# omni-usb_1_00a.net
KiCad netlist of a schematic drawn in EAGLE
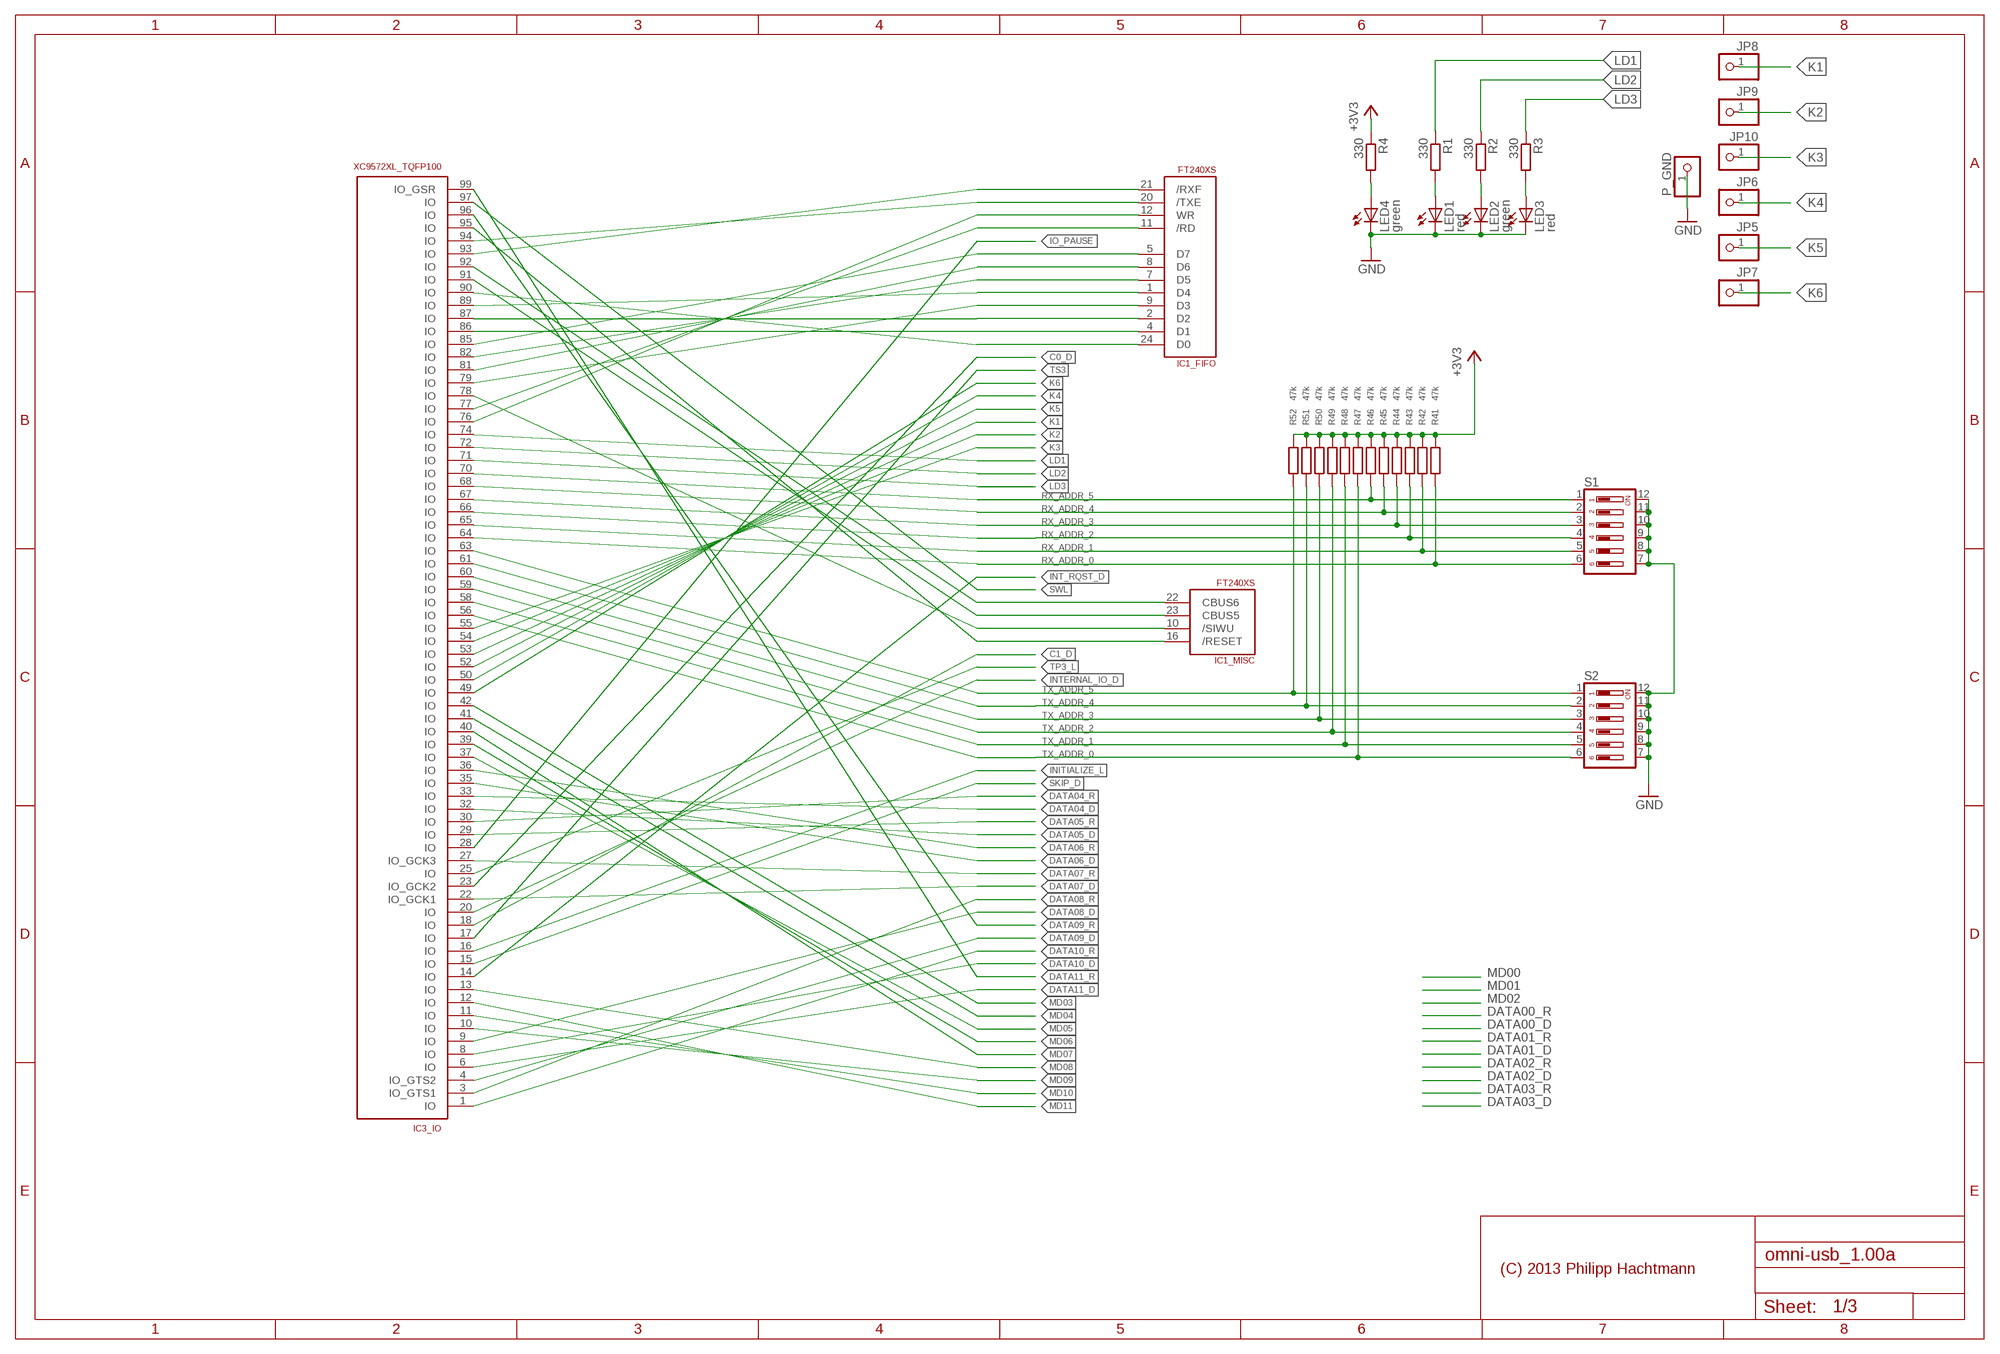
[diagram p0: schematic, sheet 1]
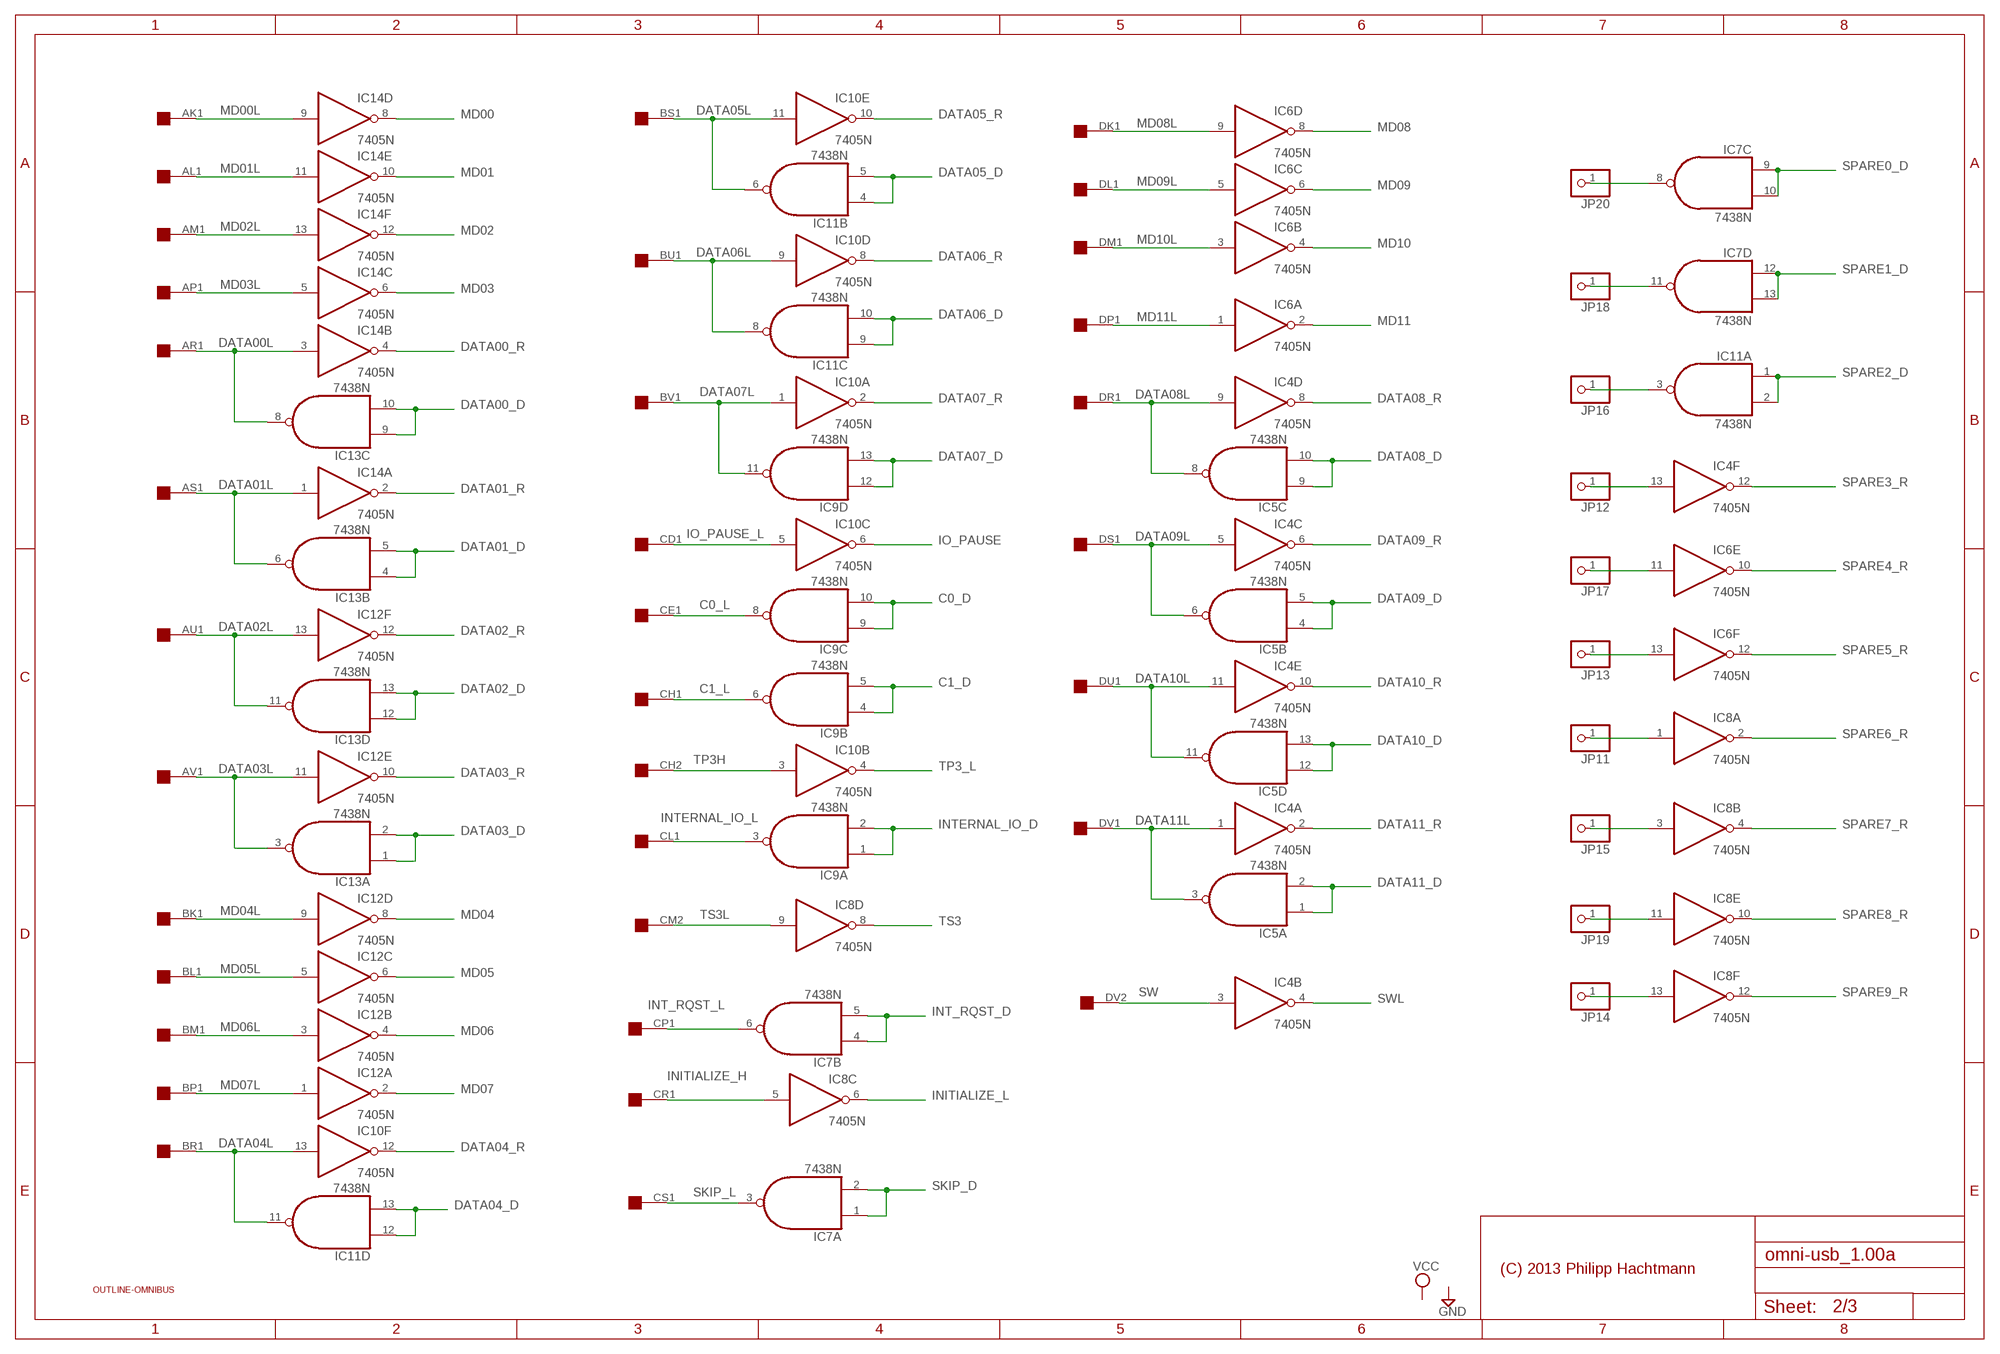
[diagram p1: schematic, sheet 2]
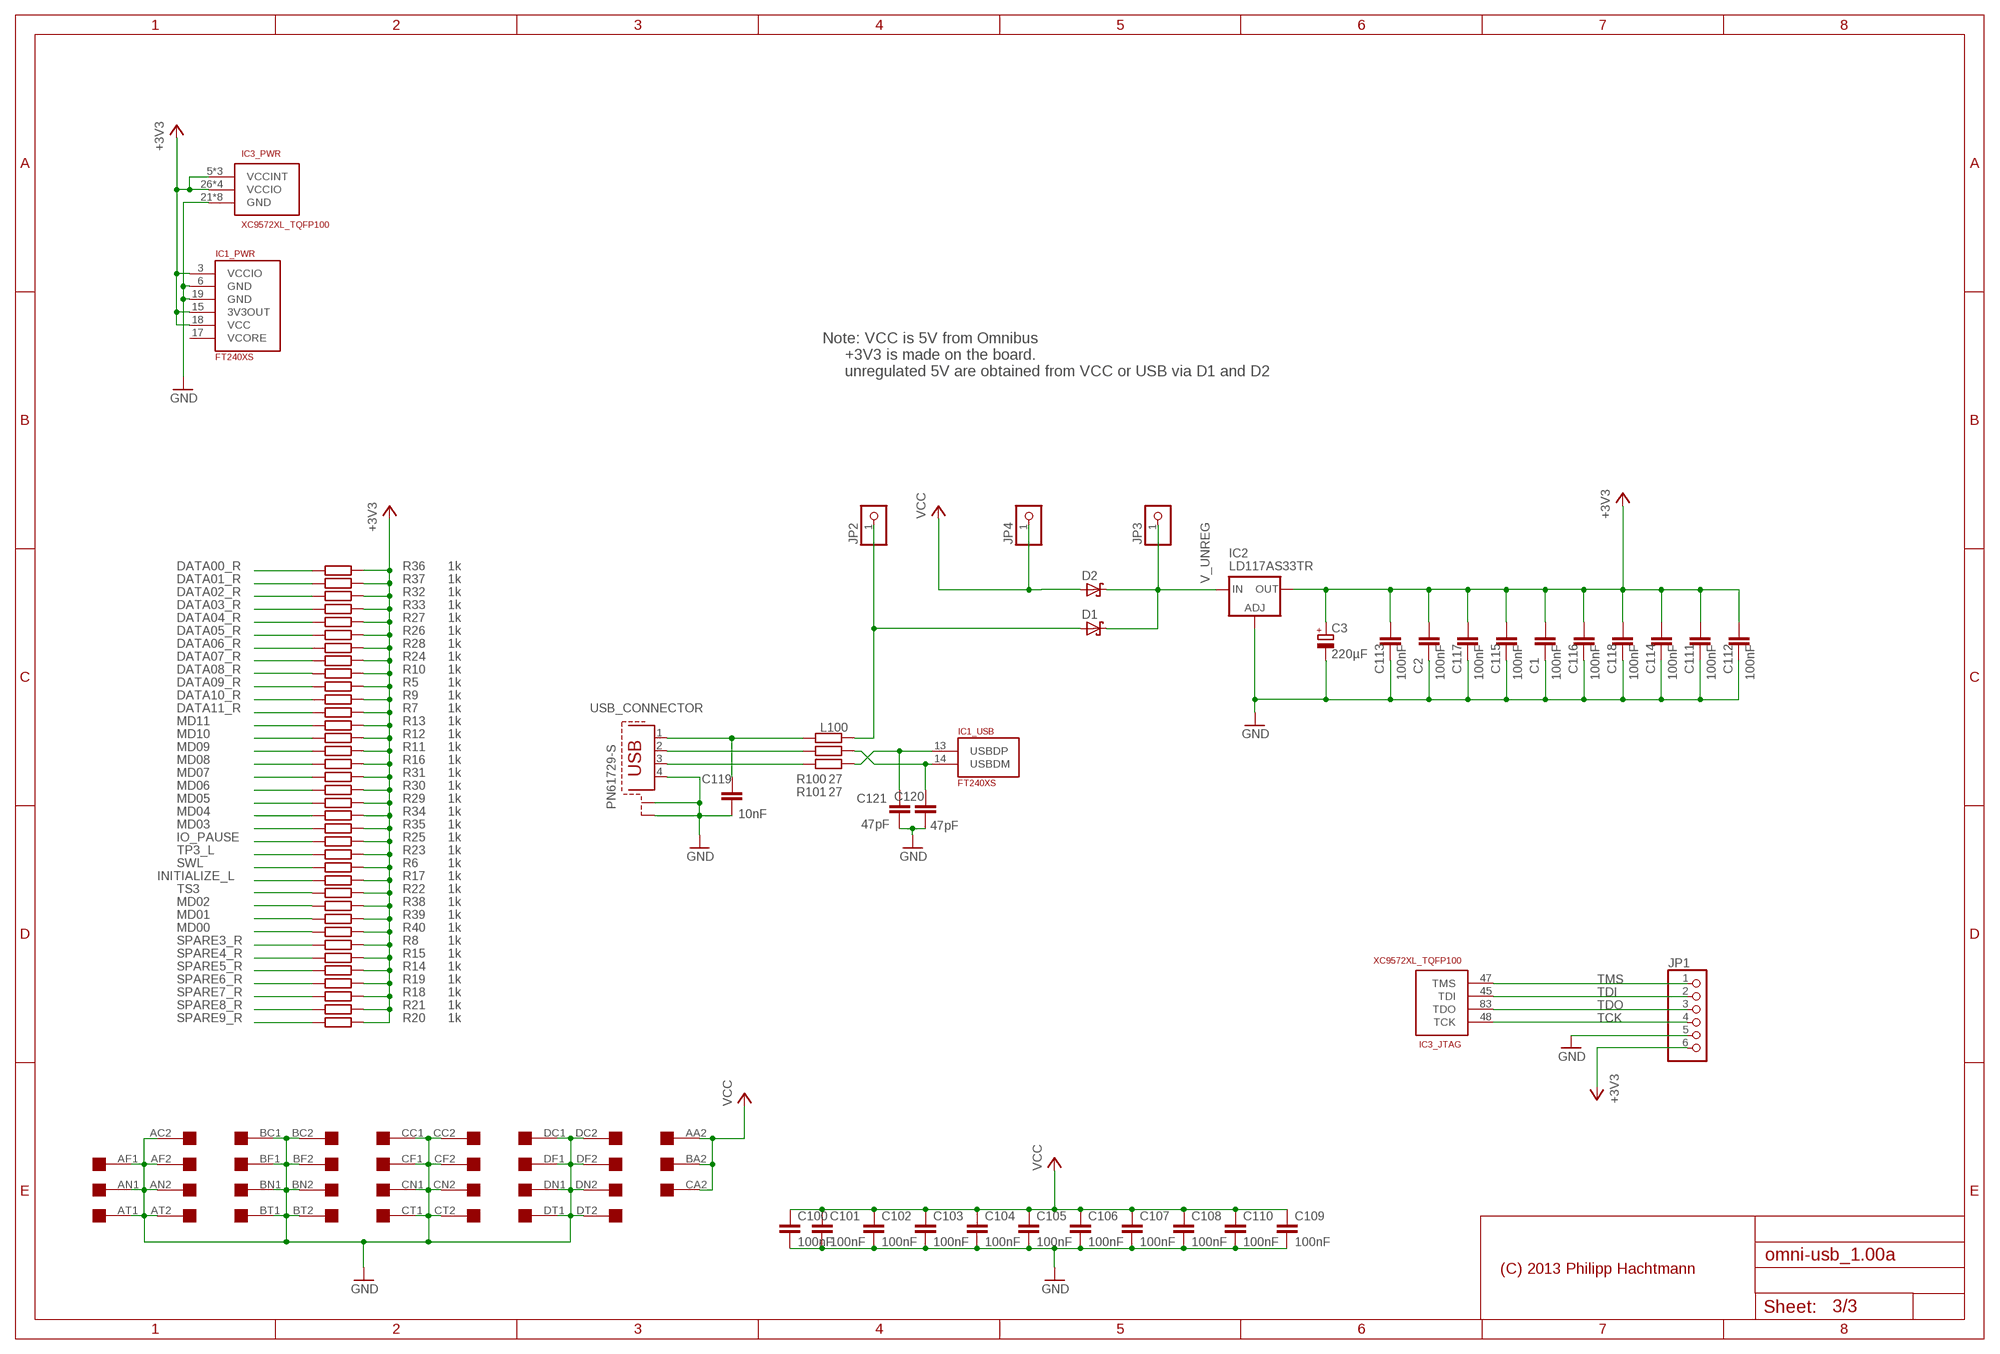
[diagram p2: schematic, sheet 3]

(export (version "E")
  (design (tool "Eeschema 10.0.6"))
  (components
    (comp (ref "C1")
      (value "100nF")
      (footprint "eagle-import:C0805")
      (fields (field (name "MF") "AVX") (field (name "MPN") "08053C104KAT2A"))
      (libsource (lib "eagle-import") (part "C-EUC0805"))
    )
    (comp (ref "C2")
      (value "100nF")
      (footprint "eagle-import:C0805")
      (fields (field (name "MF") "AVX") (field (name "MPN") "08053C104KAT2A"))
      (libsource (lib "eagle-import") (part "C-EUC0805"))
    )
    (comp (ref "C3")
      (value "220µF")
      (footprint "eagle-import:SANYO-OSCON_SMD_F8")
      (fields (field (name "MF") "MULTICOMP") (field (name "MPN") "MCEEL10V227M8X10.5"))
      (libsource (lib "eagle-import") (part "CPOL-EUSANYO_SMD_F8"))
    )
    (comp (ref "C100")
      (value "100nF")
      (footprint "eagle-import:C0805")
      (fields (field (name "MF") "AVX") (field (name "MPN") "08053C104KAT2A"))
      (libsource (lib "eagle-import") (part "C-EUC0805"))
    )
    (comp (ref "C101")
      (value "100nF")
      (footprint "eagle-import:C0805")
      (fields (field (name "MF") "AVX") (field (name "MPN") "08053C104KAT2A"))
      (libsource (lib "eagle-import") (part "C-EUC0805"))
    )
    (comp (ref "C102")
      (value "100nF")
      (footprint "eagle-import:C0805")
      (fields (field (name "MF") "AVX") (field (name "MPN") "08053C104KAT2A"))
      (libsource (lib "eagle-import") (part "C-EUC0805"))
    )
    (comp (ref "C103")
      (value "100nF")
      (footprint "eagle-import:C0805")
      (fields (field (name "MF") "AVX") (field (name "MPN") "08053C104KAT2A"))
      (libsource (lib "eagle-import") (part "C-EUC0805"))
    )
    (comp (ref "C104")
      (value "100nF")
      (footprint "eagle-import:C0805")
      (fields (field (name "MF") "AVX") (field (name "MPN") "08053C104KAT2A"))
      (libsource (lib "eagle-import") (part "C-EUC0805"))
    )
    (comp (ref "C105")
      (value "100nF")
      (footprint "eagle-import:C0805")
      (fields (field (name "MF") "AVX") (field (name "MPN") "08053C104KAT2A"))
      (libsource (lib "eagle-import") (part "C-EUC0805"))
    )
    (comp (ref "C106")
      (value "100nF")
      (footprint "eagle-import:C0805")
      (fields (field (name "MF") "AVX") (field (name "MPN") "08053C104KAT2A"))
      (libsource (lib "eagle-import") (part "C-EUC0805"))
    )
    (comp (ref "C107")
      (value "100nF")
      (footprint "eagle-import:C0805")
      (fields (field (name "MF") "AVX") (field (name "MPN") "08053C104KAT2A"))
      (libsource (lib "eagle-import") (part "C-EUC0805"))
    )
    (comp (ref "C108")
      (value "100nF")
      (footprint "eagle-import:C0805")
      (fields (field (name "MF") "AVX") (field (name "MPN") "08053C104KAT2A"))
      (libsource (lib "eagle-import") (part "C-EUC0805"))
    )
    (comp (ref "C109")
      (value "100nF")
      (footprint "eagle-import:C0805")
      (fields (field (name "MF") "AVX") (field (name "MPN") "08053C104KAT2A"))
      (libsource (lib "eagle-import") (part "C-EUC0805"))
    )
    (comp (ref "C110")
      (value "100nF")
      (footprint "eagle-import:C0805")
      (fields (field (name "MF") "AVX") (field (name "MPN") "08053C104KAT2A"))
      (libsource (lib "eagle-import") (part "C-EUC0805"))
    )
    (comp (ref "C111")
      (value "100nF")
      (footprint "eagle-import:C0805")
      (fields (field (name "MF") "AVX") (field (name "MPN") "08053C104KAT2A"))
      (libsource (lib "eagle-import") (part "C-EUC0805"))
    )
    (comp (ref "C112")
      (value "100nF")
      (footprint "eagle-import:C0805")
      (fields (field (name "MF") "AVX") (field (name "MPN") "08053C104KAT2A"))
      (libsource (lib "eagle-import") (part "C-EUC0805"))
    )
    (comp (ref "C113")
      (value "100nF")
      (footprint "eagle-import:C0805")
      (fields (field (name "MF") "AVX") (field (name "MPN") "08053C104KAT2A"))
      (libsource (lib "eagle-import") (part "C-EUC0805"))
    )
    (comp (ref "C114")
      (value "100nF")
      (footprint "eagle-import:C0805")
      (fields (field (name "MF") "AVX") (field (name "MPN") "08053C104KAT2A"))
      (libsource (lib "eagle-import") (part "C-EUC0805"))
    )
    (comp (ref "C115")
      (value "100nF")
      (footprint "eagle-import:C0805")
      (fields (field (name "MF") "AVX") (field (name "MPN") "08053C104KAT2A"))
      (libsource (lib "eagle-import") (part "C-EUC0805"))
    )
    (comp (ref "C116")
      (value "100nF")
      (footprint "eagle-import:C0805")
      (fields (field (name "MF") "AVX") (field (name "MPN") "08053C104KAT2A"))
      (libsource (lib "eagle-import") (part "C-EUC0805"))
    )
    (comp (ref "C117")
      (value "100nF")
      (footprint "eagle-import:C0805")
      (fields (field (name "MF") "AVX") (field (name "MPN") "08053C104KAT2A"))
      (libsource (lib "eagle-import") (part "C-EUC0805"))
    )
    (comp (ref "C118")
      (value "100nF")
      (footprint "eagle-import:C0805")
      (fields (field (name "MF") "AVX") (field (name "MPN") "08053C104KAT2A"))
      (libsource (lib "eagle-import") (part "C-EUC0805"))
    )
    (comp (ref "C119")
      (value "10nF")
      (footprint "eagle-import:C0805")
      (fields (field (name "MF") "AVX") (field (name "MPN") "08055C103KAT2A"))
      (libsource (lib "eagle-import") (part "C-EUC0805"))
    )
    (comp (ref "C120")
      (value "47pF")
      (footprint "eagle-import:C0805")
      (fields (field (name "MF") "MULTICOMP") (field (name "MPN") "MCCA000326"))
      (libsource (lib "eagle-import") (part "C-EUC0805"))
    )
    (comp (ref "C121")
      (value "47pF")
      (footprint "eagle-import:C0805")
      (fields (field (name "MF") "MULTICOMP") (field (name "MPN") "MCCA000326"))
      (libsource (lib "eagle-import") (part "C-EUC0805"))
    )
    (comp (ref "D1")
      (value "SCHOTTKY-DIODESMD")
      (footprint "eagle-import:SMB")
      (fields (field (name "MF") "INFINEON") (field (name "MPN") "BAT165"))
      (libsource (lib "eagle-import") (part "SCHOTTKY-DIODESMD"))
    )
    (comp (ref "D2")
      (value "SCHOTTKY-DIODESMD")
      (footprint "eagle-import:SMB")
      (fields (field (name "MF") "INFINEON") (field (name "MPN") "BAT165"))
      (libsource (lib "eagle-import") (part "SCHOTTKY-DIODESMD"))
    )
    (comp (ref "IC1")
      (value "FT240XS")
      (footprint "eagle-import:TSSOP24")
      (fields (field (name "MF") "FTDI") (field (name "MPN") "FT240XS") (field (name "OC_FARNELL") "2081332"))
      (libsource (lib "eagle-import") (part "FT240XS"))
    )
    (comp (ref "IC2")
      (value "LD117AS33TR")
      (footprint "eagle-import:SOT223")
      (fields (field (name "MF") "TEXAS INSTRUMENTS") (field (name "MPN") "TLV1117-33CDCY"))
      (libsource (lib "eagle-import") (part "LD117A?S33TR"))
    )
    (comp (ref "IC3")
      (value "XC9572XL_TQFP100")
      (footprint "eagle-import:TQ100")
      (fields
        (field (name "MF") "XILINX")
        (field (name "MPN") "XC9572XL-10TQG100C")
        (field (name "OC_FARNELL") "1193233")
      )
      (libsource (lib "eagle-import") (part "XC9572XL_TQFP100"))
    )
    (comp (ref "JP1")
      (value "PINHD-1X6/90")
      (footprint "eagle-import:1X06_90")
      (fields (field (name "MF") "MULTICOMP") (field (name "MPN") "MC34751"))
      (libsource (lib "eagle-import") (part "PINHD-1X6/90"))
    )
    (comp (ref "JP2")
      (value "PINHD-1X1")
      (footprint "eagle-import:1X01")
      (libsource (lib "eagle-import") (part "PINHD-1X1"))
    )
    (comp (ref "JP3")
      (value "PINHD-1X1")
      (footprint "eagle-import:1X01")
      (libsource (lib "eagle-import") (part "PINHD-1X1"))
    )
    (comp (ref "JP4")
      (value "PINHD-1X1")
      (footprint "eagle-import:1X01")
      (libsource (lib "eagle-import") (part "PINHD-1X1"))
    )
    (comp (ref "L100")
      (value "R-EU_R0805")
      (footprint "eagle-import:R0805")
      (libsource (lib "eagle-import") (part "R-EU_R0805"))
    )
    (comp (ref "R5")
      (value "1k")
      (footprint "eagle-import:R0805")
      (fields (field (name "MF") "PANASONIC") (field (name "MPN") "ERJ6GEYJ102V"))
      (libsource (lib "eagle-import") (part "R-EU_R0805"))
    )
    (comp (ref "R6")
      (value "1k")
      (footprint "eagle-import:R0805")
      (fields (field (name "MF") "PANASONIC") (field (name "MPN") "ERJ6GEYJ102V"))
      (libsource (lib "eagle-import") (part "R-EU_R0805"))
    )
    (comp (ref "R7")
      (value "1k")
      (footprint "eagle-import:R0805")
      (fields (field (name "MF") "PANASONIC") (field (name "MPN") "ERJ6GEYJ102V"))
      (libsource (lib "eagle-import") (part "R-EU_R0805"))
    )
    (comp (ref "R8")
      (value "1k")
      (footprint "eagle-import:R0805")
      (fields (field (name "MF") "PANASONIC") (field (name "MPN") "ERJ6GEYJ102V"))
      (libsource (lib "eagle-import") (part "R-EU_R0805"))
    )
    (comp (ref "R9")
      (value "1k")
      (footprint "eagle-import:R0805")
      (fields (field (name "MF") "PANASONIC") (field (name "MPN") "ERJ6GEYJ102V"))
      (libsource (lib "eagle-import") (part "R-EU_R0805"))
    )
    (comp (ref "R10")
      (value "1k")
      (footprint "eagle-import:R0805")
      (fields (field (name "MF") "PANASONIC") (field (name "MPN") "ERJ6GEYJ102V"))
      (libsource (lib "eagle-import") (part "R-EU_R0805"))
    )
    (comp (ref "R11")
      (value "1k")
      (footprint "eagle-import:R0805")
      (fields (field (name "MF") "PANASONIC") (field (name "MPN") "ERJ6GEYJ102V"))
      (libsource (lib "eagle-import") (part "R-EU_R0805"))
    )
    (comp (ref "R12")
      (value "1k")
      (footprint "eagle-import:R0805")
      (fields (field (name "MF") "PANASONIC") (field (name "MPN") "ERJ6GEYJ102V"))
      (libsource (lib "eagle-import") (part "R-EU_R0805"))
    )
    (comp (ref "R13")
      (value "1k")
      (footprint "eagle-import:R0805")
      (fields (field (name "MF") "PANASONIC") (field (name "MPN") "ERJ6GEYJ102V"))
      (libsource (lib "eagle-import") (part "R-EU_R0805"))
    )
    (comp (ref "R14")
      (value "1k")
      (footprint "eagle-import:R0805")
      (fields (field (name "MF") "PANASONIC") (field (name "MPN") "ERJ6GEYJ102V"))
      (libsource (lib "eagle-import") (part "R-EU_R0805"))
    )
    (comp (ref "R15")
      (value "1k")
      (footprint "eagle-import:R0805")
      (fields (field (name "MF") "PANASONIC") (field (name "MPN") "ERJ6GEYJ102V"))
      (libsource (lib "eagle-import") (part "R-EU_R0805"))
    )
    (comp (ref "R16")
      (value "1k")
      (footprint "eagle-import:R0805")
      (fields (field (name "MF") "PANASONIC") (field (name "MPN") "ERJ6GEYJ102V"))
      (libsource (lib "eagle-import") (part "R-EU_R0805"))
    )
    (comp (ref "R17")
      (value "1k")
      (footprint "eagle-import:R0805")
      (fields (field (name "MF") "PANASONIC") (field (name "MPN") "ERJ6GEYJ102V"))
      (libsource (lib "eagle-import") (part "R-EU_R0805"))
    )
    (comp (ref "R18")
      (value "1k")
      (footprint "eagle-import:R0805")
      (fields (field (name "MF") "PANASONIC") (field (name "MPN") "ERJ6GEYJ102V"))
      (libsource (lib "eagle-import") (part "R-EU_R0805"))
    )
    (comp (ref "R19")
      (value "1k")
      (footprint "eagle-import:R0805")
      (fields (field (name "MF") "PANASONIC") (field (name "MPN") "ERJ6GEYJ102V"))
      (libsource (lib "eagle-import") (part "R-EU_R0805"))
    )
    (comp (ref "R20")
      (value "1k")
      (footprint "eagle-import:R0805")
      (fields (field (name "MF") "PANASONIC") (field (name "MPN") "ERJ6GEYJ102V"))
      (libsource (lib "eagle-import") (part "R-EU_R0805"))
    )
    (comp (ref "R21")
      (value "1k")
      (footprint "eagle-import:R0805")
      (fields (field (name "MF") "PANASONIC") (field (name "MPN") "ERJ6GEYJ102V"))
      (libsource (lib "eagle-import") (part "R-EU_R0805"))
    )
    (comp (ref "R22")
      (value "1k")
      (footprint "eagle-import:R0805")
      (fields (field (name "MF") "PANASONIC") (field (name "MPN") "ERJ6GEYJ102V"))
      (libsource (lib "eagle-import") (part "R-EU_R0805"))
    )
    (comp (ref "R23")
      (value "1k")
      (footprint "eagle-import:R0805")
      (fields (field (name "MF") "PANASONIC") (field (name "MPN") "ERJ6GEYJ102V"))
      (libsource (lib "eagle-import") (part "R-EU_R0805"))
    )
    (comp (ref "R24")
      (value "1k")
      (footprint "eagle-import:R0805")
      (fields (field (name "MF") "PANASONIC") (field (name "MPN") "ERJ6GEYJ102V"))
      (libsource (lib "eagle-import") (part "R-EU_R0805"))
    )
    (comp (ref "R25")
      (value "1k")
      (footprint "eagle-import:R0805")
      (fields (field (name "MF") "PANASONIC") (field (name "MPN") "ERJ6GEYJ102V"))
      (libsource (lib "eagle-import") (part "R-EU_R0805"))
    )
    (comp (ref "R26")
      (value "1k")
      (footprint "eagle-import:R0805")
      (fields (field (name "MF") "PANASONIC") (field (name "MPN") "ERJ6GEYJ102V"))
      (libsource (lib "eagle-import") (part "R-EU_R0805"))
    )
    (comp (ref "R27")
      (value "1k")
      (footprint "eagle-import:R0805")
      (fields (field (name "MF") "PANASONIC") (field (name "MPN") "ERJ6GEYJ102V"))
      (libsource (lib "eagle-import") (part "R-EU_R0805"))
    )
    (comp (ref "R28")
      (value "1k")
      (footprint "eagle-import:R0805")
      (fields (field (name "MF") "PANASONIC") (field (name "MPN") "ERJ6GEYJ102V"))
      (libsource (lib "eagle-import") (part "R-EU_R0805"))
    )
    (comp (ref "R29")
      (value "1k")
      (footprint "eagle-import:R0805")
      (fields (field (name "MF") "PANASONIC") (field (name "MPN") "ERJ6GEYJ102V"))
      (libsource (lib "eagle-import") (part "R-EU_R0805"))
    )
    (comp (ref "R30")
      (value "1k")
      (footprint "eagle-import:R0805")
      (fields (field (name "MF") "PANASONIC") (field (name "MPN") "ERJ6GEYJ102V"))
      (libsource (lib "eagle-import") (part "R-EU_R0805"))
    )
    (comp (ref "R31")
      (value "1k")
      (footprint "eagle-import:R0805")
      (fields (field (name "MF") "PANASONIC") (field (name "MPN") "ERJ6GEYJ102V"))
      (libsource (lib "eagle-import") (part "R-EU_R0805"))
    )
    (comp (ref "R32")
      (value "1k")
      (footprint "eagle-import:R0805")
      (fields (field (name "MF") "PANASONIC") (field (name "MPN") "ERJ6GEYJ102V"))
      (libsource (lib "eagle-import") (part "R-EU_R0805"))
    )
    (comp (ref "R33")
      (value "1k")
      (footprint "eagle-import:R0805")
      (fields (field (name "MF") "PANASONIC") (field (name "MPN") "ERJ6GEYJ102V"))
      (libsource (lib "eagle-import") (part "R-EU_R0805"))
    )
    (comp (ref "R34")
      (value "1k")
      (footprint "eagle-import:R0805")
      (fields (field (name "MF") "PANASONIC") (field (name "MPN") "ERJ6GEYJ102V"))
      (libsource (lib "eagle-import") (part "R-EU_R0805"))
    )
    (comp (ref "R35")
      (value "1k")
      (footprint "eagle-import:R0805")
      (fields (field (name "MF") "PANASONIC") (field (name "MPN") "ERJ6GEYJ102V"))
      (libsource (lib "eagle-import") (part "R-EU_R0805"))
    )
    (comp (ref "R36")
      (value "1k")
      (footprint "eagle-import:R0805")
      (fields (field (name "MF") "PANASONIC") (field (name "MPN") "ERJ6GEYJ102V"))
      (libsource (lib "eagle-import") (part "R-EU_R0805"))
    )
    (comp (ref "R37")
      (value "1k")
      (footprint "eagle-import:R0805")
      (fields (field (name "MF") "PANASONIC") (field (name "MPN") "ERJ6GEYJ102V"))
      (libsource (lib "eagle-import") (part "R-EU_R0805"))
    )
    (comp (ref "R38")
      (value "1k")
      (footprint "eagle-import:R0805")
      (fields (field (name "MF") "PANASONIC") (field (name "MPN") "ERJ6GEYJ102V"))
      (libsource (lib "eagle-import") (part "R-EU_R0805"))
    )
    (comp (ref "R39")
      (value "1k")
      (footprint "eagle-import:R0805")
      (fields (field (name "MF") "PANASONIC") (field (name "MPN") "ERJ6GEYJ102V"))
      (libsource (lib "eagle-import") (part "R-EU_R0805"))
    )
    (comp (ref "R40")
      (value "1k")
      (footprint "eagle-import:R0805")
      (fields (field (name "MF") "PANASONIC") (field (name "MPN") "ERJ6GEYJ102V"))
      (libsource (lib "eagle-import") (part "R-EU_R0805"))
    )
    (comp (ref "R100")
      (value "27")
      (footprint "eagle-import:R0805")
      (fields (field (name "MF") "PANASONIC") (field (name "MPN") "ERJ6ENF2742V"))
      (libsource (lib "eagle-import") (part "R-EU_R0805"))
    )
    (comp (ref "R101")
      (value "27")
      (footprint "eagle-import:R0805")
      (fields (field (name "MF") "PANASONIC") (field (name "MPN") "ERJ6ENF2742V"))
      (libsource (lib "eagle-import") (part "R-EU_R0805"))
    )
    (comp (ref "U$2")
      (value "QUAD")
      (footprint "eagle-import:EDGE-CON8")
      (fields (field (name "OC_FARNELL") "unknown"))
      (libsource (lib "eagle-import") (part "QUAD"))
    )
    (comp (ref "USB_CONNECTOR")
      (value "PN61729-S")
      (footprint "eagle-import:PN61729-S")
      (fields
        (field (name "MF") "MULTICOMP")
        (field (name "MPN") "MC32596")
        (field (name "OC_FARNELL") "1696537")
      )
      (libsource (lib "eagle-import") (part "PN61729-S"))
    )
    (comp (ref "IC4")
      (value "7405N")
      (footprint "eagle-import:DIL14")
      (fields
        (field (name "MF") "TEXAS INSTRUMENTS")
        (field (name "MPN") "SN74AHC05N")
        (field (name "OC_FARNELL") "1749925")
      )
      (libsource (lib "eagle-import") (part "7405N"))
    )
    (comp (ref "IC5")
      (value "7438N")
      (footprint "eagle-import:DIL14")
      (fields
        (field (name "MF") "TEXAS INSTRUMENTS")
        (field (name "MPN") "SN7438N")
        (field (name "OC_FARNELL") "1607804")
      )
      (libsource (lib "eagle-import") (part "7438N"))
    )
    (comp (ref "IC6")
      (value "7405N")
      (footprint "eagle-import:DIL14")
      (fields
        (field (name "MF") "TEXAS INSTRUMENTS")
        (field (name "MPN") "SN74AHC05N")
        (field (name "OC_FARNELL") "1749925")
      )
      (libsource (lib "eagle-import") (part "7405N"))
    )
    (comp (ref "IC7")
      (value "7438N")
      (footprint "eagle-import:DIL14")
      (fields
        (field (name "MF") "TEXAS INSTRUMENTS")
        (field (name "MPN") "SN7438N")
        (field (name "OC_FARNELL") "1607804")
      )
      (libsource (lib "eagle-import") (part "7438N"))
    )
    (comp (ref "IC8")
      (value "7405N")
      (footprint "eagle-import:DIL14")
      (fields
        (field (name "MF") "TEXAS INSTRUMENTS")
        (field (name "MPN") "SN74AHC05N")
        (field (name "OC_FARNELL") "1749925")
      )
      (libsource (lib "eagle-import") (part "7405N"))
    )
    (comp (ref "IC9")
      (value "7438N")
      (footprint "eagle-import:DIL14")
      (fields
        (field (name "MF") "TEXAS INSTRUMENTS")
        (field (name "MPN") "SN7438N")
        (field (name "OC_FARNELL") "1607804")
      )
      (libsource (lib "eagle-import") (part "7438N"))
    )
    (comp (ref "IC10")
      (value "7405N")
      (footprint "eagle-import:DIL14")
      (fields
        (field (name "MF") "TEXAS INSTRUMENTS")
        (field (name "MPN") "SN74AHC05N")
        (field (name "OC_FARNELL") "1749925")
      )
      (libsource (lib "eagle-import") (part "7405N"))
    )
    (comp (ref "IC11")
      (value "7438N")
      (footprint "eagle-import:DIL14")
      (fields
        (field (name "MF") "TEXAS INSTRUMENTS")
        (field (name "MPN") "SN7438N")
        (field (name "OC_FARNELL") "1607804")
      )
      (libsource (lib "eagle-import") (part "7438N"))
    )
    (comp (ref "IC12")
      (value "7405N")
      (footprint "eagle-import:DIL14")
      (fields
        (field (name "MF") "TEXAS INSTRUMENTS")
        (field (name "MPN") "SN74AHC05N")
        (field (name "OC_FARNELL") "1749925")
      )
      (libsource (lib "eagle-import") (part "7405N"))
    )
    (comp (ref "IC13")
      (value "7438N")
      (footprint "eagle-import:DIL14")
      (fields
        (field (name "MF") "TEXAS INSTRUMENTS")
        (field (name "MPN") "SN7438N")
        (field (name "OC_FARNELL") "1607804")
      )
      (libsource (lib "eagle-import") (part "7438N"))
    )
    (comp (ref "IC14")
      (value "7405N")
      (footprint "eagle-import:DIL14")
      (fields
        (field (name "MF") "TEXAS INSTRUMENTS")
        (field (name "MPN") "SN74AHC05N")
        (field (name "OC_FARNELL") "1749925")
      )
      (libsource (lib "eagle-import") (part "7405N"))
    )
    (comp (ref "JP11")
      (value "PINHD-1X1")
      (footprint "eagle-import:1X01")
      (libsource (lib "eagle-import") (part "PINHD-1X1"))
    )
    (comp (ref "JP12")
      (value "PINHD-1X1")
      (footprint "eagle-import:1X01")
      (libsource (lib "eagle-import") (part "PINHD-1X1"))
    )
    (comp (ref "JP13")
      (value "PINHD-1X1")
      (footprint "eagle-import:1X01")
      (libsource (lib "eagle-import") (part "PINHD-1X1"))
    )
    (comp (ref "JP14")
      (value "PINHD-1X1")
      (footprint "eagle-import:1X01")
      (libsource (lib "eagle-import") (part "PINHD-1X1"))
    )
    (comp (ref "JP15")
      (value "PINHD-1X1")
      (footprint "eagle-import:1X01")
      (libsource (lib "eagle-import") (part "PINHD-1X1"))
    )
    (comp (ref "JP16")
      (value "PINHD-1X1")
      (footprint "eagle-import:1X01")
      (libsource (lib "eagle-import") (part "PINHD-1X1"))
    )
    (comp (ref "JP17")
      (value "PINHD-1X1")
      (footprint "eagle-import:1X01")
      (libsource (lib "eagle-import") (part "PINHD-1X1"))
    )
    (comp (ref "JP18")
      (value "PINHD-1X1")
      (footprint "eagle-import:1X01")
      (libsource (lib "eagle-import") (part "PINHD-1X1"))
    )
    (comp (ref "JP19")
      (value "PINHD-1X1")
      (footprint "eagle-import:1X01")
      (libsource (lib "eagle-import") (part "PINHD-1X1"))
    )
    (comp (ref "JP20")
      (value "PINHD-1X1")
      (footprint "eagle-import:1X01")
      (libsource (lib "eagle-import") (part "PINHD-1X1"))
    )
    (comp (ref "U$1")
      (value "OUTLINE-OMNIBUS")
      (footprint "eagle-import:OMNIBUS")
      (libsource (lib "eagle-import") (part "OUTLINE-OMNIBUS"))
    )
    (comp (ref "JP5")
      (value "PINHD-1X1")
      (footprint "eagle-import:1X01")
      (libsource (lib "eagle-import") (part "PINHD-1X1"))
    )
    (comp (ref "JP6")
      (value "PINHD-1X1")
      (footprint "eagle-import:1X01")
      (libsource (lib "eagle-import") (part "PINHD-1X1"))
    )
    (comp (ref "JP7")
      (value "PINHD-1X1")
      (footprint "eagle-import:1X01")
      (libsource (lib "eagle-import") (part "PINHD-1X1"))
    )
    (comp (ref "JP8")
      (value "PINHD-1X1")
      (footprint "eagle-import:1X01")
      (libsource (lib "eagle-import") (part "PINHD-1X1"))
    )
    (comp (ref "JP9")
      (value "PINHD-1X1")
      (footprint "eagle-import:1X01")
      (libsource (lib "eagle-import") (part "PINHD-1X1"))
    )
    (comp (ref "JP10")
      (value "PINHD-1X1")
      (footprint "eagle-import:1X01")
      (libsource (lib "eagle-import") (part "PINHD-1X1"))
    )
    (comp (ref "LED1")
      (value "red")
      (footprint "eagle-import:CHIPLED_0805")
      (fields (field (name "MF") "KINGBRIGHT") (field (name "MPN") "KP-2012SRC-PRV"))
      (libsource (lib "eagle-import") (part "LEDCHIPLED_0805"))
    )
    (comp (ref "LED2")
      (value "green")
      (footprint "eagle-import:CHIPLED_0805")
      (fields (field (name "MF") "KINGBRIGHT") (field (name "MPN") "KPT-2012CGCK"))
      (libsource (lib "eagle-import") (part "LEDCHIPLED_0805"))
    )
    (comp (ref "LED3")
      (value "red")
      (footprint "eagle-import:CHIPLED_0805")
      (fields (field (name "MF") "KINGBRIGHT") (field (name "MPN") "KP-2012SRC-PRV"))
      (libsource (lib "eagle-import") (part "LEDCHIPLED_0805"))
    )
    (comp (ref "LED4")
      (value "green")
      (footprint "eagle-import:CHIPLED_0805")
      (fields (field (name "MF") "KINGBRIGHT") (field (name "MPN") "KPT-2012CGCK"))
      (libsource (lib "eagle-import") (part "LEDCHIPLED_0805"))
    )
    (comp (ref "P_GND")
      (value "PINHD-1X1")
      (footprint "eagle-import:1X01")
      (libsource (lib "eagle-import") (part "PINHD-1X1"))
    )
    (comp (ref "R1")
      (value "330")
      (footprint "eagle-import:R0805")
      (libsource (lib "eagle-import") (part "R-EU_R0805"))
    )
    (comp (ref "R2")
      (value "330")
      (footprint "eagle-import:R0805")
      (libsource (lib "eagle-import") (part "R-EU_R0805"))
    )
    (comp (ref "R3")
      (value "330")
      (footprint "eagle-import:R0805")
      (libsource (lib "eagle-import") (part "R-EU_R0805"))
    )
    (comp (ref "R4")
      (value "330")
      (footprint "eagle-import:R0805")
      (libsource (lib "eagle-import") (part "R-EU_R0805"))
    )
    (comp (ref "R41")
      (value "47k")
      (footprint "eagle-import:R0805")
      (fields (field (name "MF") "PANASONIC") (field (name "MPN") "ERJ6GEYJ473V"))
      (libsource (lib "eagle-import") (part "R-EU_R0805"))
    )
    (comp (ref "R42")
      (value "47k")
      (footprint "eagle-import:R0805")
      (fields (field (name "MF") "PANASONIC") (field (name "MPN") "ERJ6GEYJ473V"))
      (libsource (lib "eagle-import") (part "R-EU_R0805"))
    )
    (comp (ref "R43")
      (value "47k")
      (footprint "eagle-import:R0805")
      (fields (field (name "MF") "PANASONIC") (field (name "MPN") "ERJ6GEYJ473V"))
      (libsource (lib "eagle-import") (part "R-EU_R0805"))
    )
    (comp (ref "R44")
      (value "47k")
      (footprint "eagle-import:R0805")
      (fields (field (name "MF") "PANASONIC") (field (name "MPN") "ERJ6GEYJ473V"))
      (libsource (lib "eagle-import") (part "R-EU_R0805"))
    )
    (comp (ref "R45")
      (value "47k")
      (footprint "eagle-import:R0805")
      (fields (field (name "MF") "PANASONIC") (field (name "MPN") "ERJ6GEYJ473V"))
      (libsource (lib "eagle-import") (part "R-EU_R0805"))
    )
    (comp (ref "R46")
      (value "47k")
      (footprint "eagle-import:R0805")
      (fields (field (name "MF") "PANASONIC") (field (name "MPN") "ERJ6GEYJ473V"))
      (libsource (lib "eagle-import") (part "R-EU_R0805"))
    )
    (comp (ref "R47")
      (value "47k")
      (footprint "eagle-import:R0805")
      (fields (field (name "MF") "PANASONIC") (field (name "MPN") "ERJ6GEYJ473V"))
      (libsource (lib "eagle-import") (part "R-EU_R0805"))
    )
    (comp (ref "R48")
      (value "47k")
      (footprint "eagle-import:R0805")
      (fields (field (name "MF") "PANASONIC") (field (name "MPN") "ERJ6GEYJ473V"))
      (libsource (lib "eagle-import") (part "R-EU_R0805"))
    )
    (comp (ref "R49")
      (value "47k")
      (footprint "eagle-import:R0805")
      (fields (field (name "MF") "PANASONIC") (field (name "MPN") "ERJ6GEYJ473V"))
      (libsource (lib "eagle-import") (part "R-EU_R0805"))
    )
    (comp (ref "R50")
      (value "47k")
      (footprint "eagle-import:R0805")
      (fields (field (name "MF") "PANASONIC") (field (name "MPN") "ERJ6GEYJ473V"))
      (libsource (lib "eagle-import") (part "R-EU_R0805"))
    )
    (comp (ref "R51")
      (value "47k")
      (footprint "eagle-import:R0805")
      (fields (field (name "MF") "PANASONIC") (field (name "MPN") "ERJ6GEYJ473V"))
      (libsource (lib "eagle-import") (part "R-EU_R0805"))
    )
    (comp (ref "R52")
      (value "47k")
      (footprint "eagle-import:R0805")
      (fields (field (name "MF") "PANASONIC") (field (name "MPN") "ERJ6GEYJ473V"))
      (libsource (lib "eagle-import") (part "R-EU_R0805"))
    )
    (comp (ref "S1")
      (value "DIP06YL")
      (footprint "eagle-import:DIP06YL")
      (fields (field (name "OC_FARNELL") "unknown"))
      (libsource (lib "eagle-import") (part "DIP06YL"))
    )
    (comp (ref "S2")
      (value "DIP06YL")
      (footprint "eagle-import:DIP06YL")
      (fields (field (name "OC_FARNELL") "unknown"))
      (libsource (lib "eagle-import") (part "DIP06YL"))
    )
  )
  (nets
    (net (code "1") (name "+3V3") (class "Default")
      (node (ref "C1") (pin "1") (pinfunction "1_1") (pintype "passive"))
      (node (ref "C111") (pin "1") (pinfunction "1_1") (pintype "passive"))
      (node (ref "C112") (pin "1") (pinfunction "1_1") (pintype "passive"))
      (node (ref "C113") (pin "1") (pinfunction "1_1") (pintype "passive"))
      (node (ref "C114") (pin "1") (pinfunction "1_1") (pintype "passive"))
      (node (ref "C115") (pin "1") (pinfunction "1_1") (pintype "passive"))
      (node (ref "C116") (pin "1") (pinfunction "1_1") (pintype "passive"))
      (node (ref "C117") (pin "1") (pinfunction "1_1") (pintype "passive"))
      (node (ref "C118") (pin "1") (pinfunction "1_1") (pintype "passive"))
      (node (ref "C2") (pin "1") (pinfunction "1_1") (pintype "passive"))
      (node (ref "C3") (pin "+") (pinfunction "+_+") (pintype "passive"))
      (node (ref "IC1") (pin "15") (pinfunction "3V3OUT_15") (pintype "output"))
      (node (ref "IC1") (pin "18") (pinfunction "VCC_18") (pintype "input"))
      (node (ref "IC1") (pin "3") (pinfunction "VCCIO_3") (pintype "input"))
      (node (ref "IC2") (pin "4") (pinfunction "OUT_4") (pintype "passive"))
      (node (ref "IC3") (pin "26") (pinfunction "VCCIO_26") (pintype "input"))
      (node (ref "IC3") (pin "38") (pinfunction "VCCIO_38") (pintype "input"))
      (node (ref "IC3") (pin "5") (pinfunction "VCCINT_5") (pintype "input"))
      (node (ref "IC3") (pin "51") (pinfunction "VCCIO_51") (pintype "input"))
      (node (ref "IC3") (pin "57") (pinfunction "VCCINT_57") (pintype "input"))
      (node (ref "IC3") (pin "88") (pinfunction "VCCIO_88") (pintype "input"))
      (node (ref "IC3") (pin "98") (pinfunction "VCCINT_98") (pintype "input"))
      (node (ref "JP1") (pin "6") (pinfunction "6_6") (pintype "passive"))
      (node (ref "R10") (pin "1") (pinfunction "1_1") (pintype "passive"))
      (node (ref "R11") (pin "1") (pinfunction "1_1") (pintype "passive"))
      (node (ref "R12") (pin "1") (pinfunction "1_1") (pintype "passive"))
      (node (ref "R13") (pin "1") (pinfunction "1_1") (pintype "passive"))
      (node (ref "R14") (pin "1") (pinfunction "1_1") (pintype "passive"))
      (node (ref "R15") (pin "1") (pinfunction "1_1") (pintype "passive"))
      (node (ref "R16") (pin "1") (pinfunction "1_1") (pintype "passive"))
      (node (ref "R17") (pin "1") (pinfunction "1_1") (pintype "passive"))
      (node (ref "R18") (pin "1") (pinfunction "1_1") (pintype "passive"))
      (node (ref "R19") (pin "1") (pinfunction "1_1") (pintype "passive"))
      (node (ref "R20") (pin "1") (pinfunction "1_1") (pintype "passive"))
      (node (ref "R21") (pin "1") (pinfunction "1_1") (pintype "passive"))
      (node (ref "R22") (pin "1") (pinfunction "1_1") (pintype "passive"))
      (node (ref "R23") (pin "1") (pinfunction "1_1") (pintype "passive"))
      (node (ref "R24") (pin "1") (pinfunction "1_1") (pintype "passive"))
      (node (ref "R25") (pin "1") (pinfunction "1_1") (pintype "passive"))
      (node (ref "R26") (pin "1") (pinfunction "1_1") (pintype "passive"))
      (node (ref "R27") (pin "1") (pinfunction "1_1") (pintype "passive"))
      (node (ref "R28") (pin "1") (pinfunction "1_1") (pintype "passive"))
      (node (ref "R29") (pin "1") (pinfunction "1_1") (pintype "passive"))
      (node (ref "R30") (pin "1") (pinfunction "1_1") (pintype "passive"))
      (node (ref "R31") (pin "1") (pinfunction "1_1") (pintype "passive"))
      (node (ref "R32") (pin "1") (pinfunction "1_1") (pintype "passive"))
      (node (ref "R33") (pin "1") (pinfunction "1_1") (pintype "passive"))
      (node (ref "R34") (pin "1") (pinfunction "1_1") (pintype "passive"))
      (node (ref "R35") (pin "1") (pinfunction "1_1") (pintype "passive"))
      (node (ref "R36") (pin "1") (pinfunction "1_1") (pintype "passive"))
      (node (ref "R37") (pin "1") (pinfunction "1_1") (pintype "passive"))
      (node (ref "R38") (pin "1") (pinfunction "1_1") (pintype "passive"))
      (node (ref "R39") (pin "1") (pinfunction "1_1") (pintype "passive"))
      (node (ref "R4") (pin "1") (pinfunction "1_1") (pintype "passive"))
      (node (ref "R40") (pin "1") (pinfunction "1_1") (pintype "passive"))
      (node (ref "R41") (pin "2") (pinfunction "2_2") (pintype "passive"))
      (node (ref "R42") (pin "2") (pinfunction "2_2") (pintype "passive"))
      (node (ref "R43") (pin "2") (pinfunction "2_2") (pintype "passive"))
      (node (ref "R44") (pin "2") (pinfunction "2_2") (pintype "passive"))
      (node (ref "R45") (pin "2") (pinfunction "2_2") (pintype "passive"))
      (node (ref "R46") (pin "2") (pinfunction "2_2") (pintype "passive"))
      (node (ref "R47") (pin "2") (pinfunction "2_2") (pintype "passive"))
      (node (ref "R48") (pin "2") (pinfunction "2_2") (pintype "passive"))
      (node (ref "R49") (pin "2") (pinfunction "2_2") (pintype "passive"))
      (node (ref "R5") (pin "1") (pinfunction "1_1") (pintype "passive"))
      (node (ref "R50") (pin "2") (pinfunction "2_2") (pintype "passive"))
      (node (ref "R51") (pin "2") (pinfunction "2_2") (pintype "passive"))
      (node (ref "R52") (pin "2") (pinfunction "2_2") (pintype "passive"))
      (node (ref "R6") (pin "1") (pinfunction "1_1") (pintype "passive"))
      (node (ref "R7") (pin "1") (pinfunction "1_1") (pintype "passive"))
      (node (ref "R8") (pin "1") (pinfunction "1_1") (pintype "passive"))
      (node (ref "R9") (pin "1") (pinfunction "1_1") (pintype "passive"))
    )
    (net (code "2") (name "C0_D") (class "Default")
      (node (ref "IC3") (pin "23") (pinfunction "IO_GCK2_23") (pintype "bidirectional"))
      (node (ref "IC9") (pin "10") (pinfunction "I1_10") (pintype "input"))
      (node (ref "IC9") (pin "9") (pinfunction "I0_9") (pintype "input"))
    )
    (net (code "3") (name "C0_L") (class "Default")
      (node (ref "IC9") (pin "8") (pinfunction "O_8") (pintype "open_collector"))
      (node (ref "U$2") (pin "CE1") (pinfunction "1_CE1") (pintype "bidirectional"))
    )
    (net (code "4") (name "C1_D") (class "Default")
      (node (ref "IC3") (pin "18") (pinfunction "IO_18") (pintype "bidirectional"))
      (node (ref "IC9") (pin "4") (pinfunction "I0_4") (pintype "input"))
      (node (ref "IC9") (pin "5") (pinfunction "I1_5") (pintype "input"))
    )
    (net (code "5") (name "C1_L") (class "Default")
      (node (ref "IC9") (pin "6") (pinfunction "O_6") (pintype "open_collector"))
      (node (ref "U$2") (pin "CH1") (pinfunction "1_CH1") (pintype "bidirectional"))
    )
    (net (code "6") (name "DATA00L") (class "Default")
      (node (ref "IC13") (pin "8") (pinfunction "O_8") (pintype "open_collector"))
      (node (ref "IC14") (pin "3") (pinfunction "I_3") (pintype "input"))
      (node (ref "U$2") (pin "AR1") (pinfunction "1_AR1") (pintype "bidirectional"))
    )
    (net (code "7") (name "DATA00_D") (class "Default")
      (node (ref "IC13") (pin "10") (pinfunction "I1_10") (pintype "input"))
      (node (ref "IC13") (pin "9") (pinfunction "I0_9") (pintype "input"))
    )
    (net (code "8") (name "DATA00_R") (class "Default")
      (node (ref "IC14") (pin "4") (pinfunction "O_4") (pintype "open_collector"))
      (node (ref "R36") (pin "2") (pinfunction "2_2") (pintype "passive"))
    )
    (net (code "9") (name "DATA01L") (class "Default")
      (node (ref "IC13") (pin "6") (pinfunction "O_6") (pintype "open_collector"))
      (node (ref "IC14") (pin "1") (pinfunction "I_1") (pintype "input"))
      (node (ref "U$2") (pin "AS1") (pinfunction "1_AS1") (pintype "bidirectional"))
    )
    (net (code "10") (name "DATA01_D") (class "Default")
      (node (ref "IC13") (pin "4") (pinfunction "I0_4") (pintype "input"))
      (node (ref "IC13") (pin "5") (pinfunction "I1_5") (pintype "input"))
    )
    (net (code "11") (name "DATA01_R") (class "Default")
      (node (ref "IC14") (pin "2") (pinfunction "O_2") (pintype "open_collector"))
      (node (ref "R37") (pin "2") (pinfunction "2_2") (pintype "passive"))
    )
    (net (code "12") (name "DATA02L") (class "Default")
      (node (ref "IC12") (pin "13") (pinfunction "I_13") (pintype "input"))
      (node (ref "IC13") (pin "11") (pinfunction "O_11") (pintype "open_collector"))
      (node (ref "U$2") (pin "AU1") (pinfunction "1_AU1") (pintype "bidirectional"))
    )
    (net (code "13") (name "DATA02_D") (class "Default")
      (node (ref "IC13") (pin "12") (pinfunction "I0_12") (pintype "input"))
      (node (ref "IC13") (pin "13") (pinfunction "I1_13") (pintype "input"))
    )
    (net (code "14") (name "DATA02_R") (class "Default")
      (node (ref "IC12") (pin "12") (pinfunction "O_12") (pintype "open_collector"))
      (node (ref "R32") (pin "2") (pinfunction "2_2") (pintype "passive"))
    )
    (net (code "15") (name "DATA03L") (class "Default")
      (node (ref "IC12") (pin "11") (pinfunction "I_11") (pintype "input"))
      (node (ref "IC13") (pin "3") (pinfunction "O_3") (pintype "open_collector"))
      (node (ref "U$2") (pin "AV1") (pinfunction "1_AV1") (pintype "bidirectional"))
    )
    (net (code "16") (name "DATA03_D") (class "Default")
      (node (ref "IC13") (pin "1") (pinfunction "I0_1") (pintype "input"))
      (node (ref "IC13") (pin "2") (pinfunction "I1_2") (pintype "input"))
    )
    (net (code "17") (name "DATA03_R") (class "Default")
      (node (ref "IC12") (pin "10") (pinfunction "O_10") (pintype "open_collector"))
      (node (ref "R33") (pin "2") (pinfunction "2_2") (pintype "passive"))
    )
    (net (code "18") (name "DATA04L") (class "Default")
      (node (ref "IC10") (pin "13") (pinfunction "I_13") (pintype "input"))
      (node (ref "IC11") (pin "11") (pinfunction "O_11") (pintype "open_collector"))
      (node (ref "U$2") (pin "BR1") (pinfunction "1_BR1") (pintype "bidirectional"))
    )
    (net (code "19") (name "DATA04_D") (class "Default")
      (node (ref "IC11") (pin "12") (pinfunction "I0_12") (pintype "input"))
      (node (ref "IC11") (pin "13") (pinfunction "I1_13") (pintype "input"))
      (node (ref "IC3") (pin "33") (pinfunction "IO_33") (pintype "bidirectional"))
    )
    (net (code "20") (name "DATA04_R") (class "Default")
      (node (ref "IC10") (pin "12") (pinfunction "O_12") (pintype "open_collector"))
      (node (ref "IC3") (pin "30") (pinfunction "IO_30") (pintype "bidirectional"))
      (node (ref "R27") (pin "2") (pinfunction "2_2") (pintype "passive"))
    )
    (net (code "21") (name "DATA05L") (class "Default")
      (node (ref "IC10") (pin "11") (pinfunction "I_11") (pintype "input"))
      (node (ref "IC11") (pin "6") (pinfunction "O_6") (pintype "open_collector"))
      (node (ref "U$2") (pin "BS1") (pinfunction "1_BS1") (pintype "bidirectional"))
    )
    (net (code "22") (name "DATA05_D") (class "Default")
      (node (ref "IC11") (pin "4") (pinfunction "I0_4") (pintype "input"))
      (node (ref "IC11") (pin "5") (pinfunction "I1_5") (pintype "input"))
      (node (ref "IC3") (pin "32") (pinfunction "IO_32") (pintype "bidirectional"))
    )
    (net (code "23") (name "DATA05_R") (class "Default")
      (node (ref "IC10") (pin "10") (pinfunction "O_10") (pintype "open_collector"))
      (node (ref "IC3") (pin "29") (pinfunction "IO_29") (pintype "bidirectional"))
      (node (ref "R26") (pin "2") (pinfunction "2_2") (pintype "passive"))
    )
    (net (code "24") (name "DATA06L") (class "Default")
      (node (ref "IC10") (pin "9") (pinfunction "I_9") (pintype "input"))
      (node (ref "IC11") (pin "8") (pinfunction "O_8") (pintype "open_collector"))
      (node (ref "U$2") (pin "BU1") (pinfunction "1_BU1") (pintype "bidirectional"))
    )
    (net (code "25") (name "DATA06_D") (class "Default")
      (node (ref "IC11") (pin "10") (pinfunction "I1_10") (pintype "input"))
      (node (ref "IC11") (pin "9") (pinfunction "I0_9") (pintype "input"))
      (node (ref "IC3") (pin "35") (pinfunction "IO_35") (pintype "bidirectional"))
    )
    (net (code "26") (name "DATA06_R") (class "Default")
      (node (ref "IC10") (pin "8") (pinfunction "O_8") (pintype "open_collector"))
      (node (ref "IC3") (pin "36") (pinfunction "IO_36") (pintype "bidirectional"))
      (node (ref "R28") (pin "2") (pinfunction "2_2") (pintype "passive"))
    )
    (net (code "27") (name "DATA07L") (class "Default")
      (node (ref "IC10") (pin "1") (pinfunction "I_1") (pintype "input"))
      (node (ref "IC9") (pin "11") (pinfunction "O_11") (pintype "open_collector"))
      (node (ref "U$2") (pin "BV1") (pinfunction "1_BV1") (pintype "bidirectional"))
    )
    (net (code "28") (name "DATA07_D") (class "Default")
      (node (ref "IC3") (pin "22") (pinfunction "IO_GCK1_22") (pintype "bidirectional"))
      (node (ref "IC9") (pin "12") (pinfunction "I0_12") (pintype "input"))
      (node (ref "IC9") (pin "13") (pinfunction "I1_13") (pintype "input"))
    )
    (net (code "29") (name "DATA07_R") (class "Default")
      (node (ref "IC10") (pin "2") (pinfunction "O_2") (pintype "open_collector"))
      (node (ref "IC3") (pin "27") (pinfunction "IO_GCK3_27") (pintype "bidirectional"))
      (node (ref "R24") (pin "2") (pinfunction "2_2") (pintype "passive"))
    )
    (net (code "30") (name "DATA08L") (class "Default")
      (node (ref "IC4") (pin "9") (pinfunction "I_9") (pintype "input"))
      (node (ref "IC5") (pin "8") (pinfunction "O_8") (pintype "open_collector"))
      (node (ref "U$2") (pin "DR1") (pinfunction "1_DR1") (pintype "bidirectional"))
    )
    (net (code "31") (name "DATA08_D") (class "Default")
      (node (ref "IC3") (pin "9") (pinfunction "IO_9") (pintype "bidirectional"))
      (node (ref "IC5") (pin "10") (pinfunction "I1_10") (pintype "input"))
      (node (ref "IC5") (pin "9") (pinfunction "I0_9") (pintype "input"))
    )
    (net (code "32") (name "DATA08_R") (class "Default")
      (node (ref "IC3") (pin "3") (pinfunction "IO_GTS1_3") (pintype "bidirectional"))
      (node (ref "IC4") (pin "8") (pinfunction "O_8") (pintype "open_collector"))
      (node (ref "R10") (pin "2") (pinfunction "2_2") (pintype "passive"))
    )
    (net (code "33") (name "DATA09L") (class "Default")
      (node (ref "IC4") (pin "5") (pinfunction "I_5") (pintype "input"))
      (node (ref "IC5") (pin "6") (pinfunction "O_6") (pintype "open_collector"))
      (node (ref "U$2") (pin "DS1") (pinfunction "1_DS1") (pintype "bidirectional"))
    )
    (net (code "34") (name "DATA09_D") (class "Default")
      (node (ref "IC3") (pin "4") (pinfunction "IO_GTS2_4") (pintype "bidirectional"))
      (node (ref "IC5") (pin "4") (pinfunction "I0_4") (pintype "input"))
      (node (ref "IC5") (pin "5") (pinfunction "I1_5") (pintype "input"))
    )
    (net (code "35") (name "DATA09_R") (class "Default")
      (node (ref "IC3") (pin "96") (pinfunction "IO_96") (pintype "bidirectional"))
      (node (ref "IC4") (pin "6") (pinfunction "O_6") (pintype "open_collector"))
      (node (ref "R5") (pin "2") (pinfunction "2_2") (pintype "passive"))
    )
    (net (code "36") (name "DATA10L") (class "Default")
      (node (ref "IC4") (pin "11") (pinfunction "I_11") (pintype "input"))
      (node (ref "IC5") (pin "11") (pinfunction "O_11") (pintype "open_collector"))
      (node (ref "U$2") (pin "DU1") (pinfunction "1_DU1") (pintype "bidirectional"))
    )
    (net (code "37") (name "DATA10_D") (class "Default")
      (node (ref "IC3") (pin "8") (pinfunction "IO_8") (pintype "bidirectional"))
      (node (ref "IC5") (pin "12") (pinfunction "I0_12") (pintype "input"))
      (node (ref "IC5") (pin "13") (pinfunction "I1_13") (pintype "input"))
    )
    (net (code "38") (name "DATA10_R") (class "Default")
      (node (ref "IC3") (pin "1") (pinfunction "IO_1") (pintype "bidirectional"))
      (node (ref "IC4") (pin "10") (pinfunction "O_10") (pintype "open_collector"))
      (node (ref "R9") (pin "2") (pinfunction "2_2") (pintype "passive"))
    )
    (net (code "39") (name "DATA11L") (class "Default")
      (node (ref "IC4") (pin "1") (pinfunction "I_1") (pintype "input"))
      (node (ref "IC5") (pin "3") (pinfunction "O_3") (pintype "open_collector"))
      (node (ref "U$2") (pin "DV1") (pinfunction "1_DV1") (pintype "bidirectional"))
    )
    (net (code "40") (name "DATA11_D") (class "Default")
      (node (ref "IC3") (pin "6") (pinfunction "IO_6") (pintype "bidirectional"))
      (node (ref "IC5") (pin "1") (pinfunction "I0_1") (pintype "input"))
      (node (ref "IC5") (pin "2") (pinfunction "I1_2") (pintype "input"))
    )
    (net (code "41") (name "DATA11_R") (class "Default")
      (node (ref "IC3") (pin "99") (pinfunction "IO_GSR_99") (pintype "bidirectional"))
      (node (ref "IC4") (pin "2") (pinfunction "O_2") (pintype "open_collector"))
      (node (ref "R7") (pin "2") (pinfunction "2_2") (pintype "passive"))
    )
    (net (code "42") (name "GND") (class "Default")
      (node (ref "C1") (pin "2") (pinfunction "2_2") (pintype "passive"))
      (node (ref "C100") (pin "2") (pinfunction "2_2") (pintype "passive"))
      (node (ref "C101") (pin "2") (pinfunction "2_2") (pintype "passive"))
      (node (ref "C102") (pin "2") (pinfunction "2_2") (pintype "passive"))
      (node (ref "C103") (pin "2") (pinfunction "2_2") (pintype "passive"))
      (node (ref "C104") (pin "2") (pinfunction "2_2") (pintype "passive"))
      (node (ref "C105") (pin "2") (pinfunction "2_2") (pintype "passive"))
      (node (ref "C106") (pin "2") (pinfunction "2_2") (pintype "passive"))
      (node (ref "C107") (pin "2") (pinfunction "2_2") (pintype "passive"))
      (node (ref "C108") (pin "2") (pinfunction "2_2") (pintype "passive"))
      (node (ref "C109") (pin "2") (pinfunction "2_2") (pintype "passive"))
      (node (ref "C110") (pin "2") (pinfunction "2_2") (pintype "passive"))
      (node (ref "C111") (pin "2") (pinfunction "2_2") (pintype "passive"))
      (node (ref "C112") (pin "2") (pinfunction "2_2") (pintype "passive"))
      (node (ref "C113") (pin "2") (pinfunction "2_2") (pintype "passive"))
      (node (ref "C114") (pin "2") (pinfunction "2_2") (pintype "passive"))
      (node (ref "C115") (pin "2") (pinfunction "2_2") (pintype "passive"))
      (node (ref "C116") (pin "2") (pinfunction "2_2") (pintype "passive"))
      (node (ref "C117") (pin "2") (pinfunction "2_2") (pintype "passive"))
      (node (ref "C118") (pin "2") (pinfunction "2_2") (pintype "passive"))
      (node (ref "C119") (pin "2") (pinfunction "2_2") (pintype "passive"))
      (node (ref "C120") (pin "2") (pinfunction "2_2") (pintype "passive"))
      (node (ref "C121") (pin "2") (pinfunction "2_2") (pintype "passive"))
      (node (ref "C2") (pin "2") (pinfunction "2_2") (pintype "passive"))
      (node (ref "C3") (pin "-") (pinfunction "-_-") (pintype "passive"))
      (node (ref "IC1") (pin "19") (pinfunction "GND_19") (pintype "power_in"))
      (node (ref "IC1") (pin "6") (pinfunction "GND_6") (pintype "power_in"))
      (node (ref "IC2") (pin "1") (pinfunction "ADJ_1") (pintype "input"))
      (node (ref "IC3") (pin "100") (pinfunction "GND_100") (pintype "input"))
      (node (ref "IC3") (pin "21") (pinfunction "GND_21") (pintype "input"))
      (node (ref "IC3") (pin "31") (pinfunction "GND_31") (pintype "input"))
      (node (ref "IC3") (pin "44") (pinfunction "GND_44") (pintype "input"))
      (node (ref "IC3") (pin "62") (pinfunction "GND_62") (pintype "input"))
      (node (ref "IC3") (pin "69") (pinfunction "GND_69") (pintype "input"))
      (node (ref "IC3") (pin "75") (pinfunction "GND_75") (pintype "input"))
      (node (ref "IC3") (pin "84") (pinfunction "GND_84") (pintype "input"))
      (node (ref "JP1") (pin "5") (pinfunction "5_5") (pintype "passive"))
      (node (ref "LED1") (pin "C") (pinfunction "C_C") (pintype "passive"))
      (node (ref "LED2") (pin "C") (pinfunction "C_C") (pintype "passive"))
      (node (ref "LED3") (pin "C") (pinfunction "C_C") (pintype "passive"))
      (node (ref "LED4") (pin "C") (pinfunction "C_C") (pintype "passive"))
      (node (ref "P_GND") (pin "1") (pinfunction "1_1") (pintype "passive"))
      (node (ref "S1") (pin "10") (pinfunction "10_10") (pintype "passive"))
      (node (ref "S1") (pin "11") (pinfunction "11_11") (pintype "passive"))
      (node (ref "S1") (pin "12") (pinfunction "12_12") (pintype "passive"))
      (node (ref "S1") (pin "7") (pinfunction "7_7") (pintype "passive"))
      (node (ref "S1") (pin "8") (pinfunction "8_8") (pintype "passive"))
      (node (ref "S1") (pin "9") (pinfunction "9_9") (pintype "passive"))
      (node (ref "S2") (pin "10") (pinfunction "10_10") (pintype "passive"))
      (node (ref "S2") (pin "11") (pinfunction "11_11") (pintype "passive"))
      (node (ref "S2") (pin "12") (pinfunction "12_12") (pintype "passive"))
      (node (ref "S2") (pin "7") (pinfunction "7_7") (pintype "passive"))
      (node (ref "S2") (pin "8") (pinfunction "8_8") (pintype "passive"))
      (node (ref "S2") (pin "9") (pinfunction "9_9") (pintype "passive"))
      (node (ref "U$2") (pin "AC2") (pinfunction "1_AC2") (pintype "bidirectional"))
      (node (ref "U$2") (pin "AF1") (pinfunction "1_AF1") (pintype "bidirectional"))
      (node (ref "U$2") (pin "AF2") (pinfunction "1_AF2") (pintype "bidirectional"))
      (node (ref "U$2") (pin "AN1") (pinfunction "1_AN1") (pintype "bidirectional"))
      (node (ref "U$2") (pin "AN2") (pinfunction "1_AN2") (pintype "bidirectional"))
      (node (ref "U$2") (pin "AT1") (pinfunction "1_AT1") (pintype "bidirectional"))
      (node (ref "U$2") (pin "AT2") (pinfunction "1_AT2") (pintype "bidirectional"))
      (node (ref "U$2") (pin "BC1") (pinfunction "1_BC1") (pintype "bidirectional"))
      (node (ref "U$2") (pin "BC2") (pinfunction "1_BC2") (pintype "bidirectional"))
      (node (ref "U$2") (pin "BF1") (pinfunction "1_BF1") (pintype "bidirectional"))
      (node (ref "U$2") (pin "BF2") (pinfunction "1_BF2") (pintype "bidirectional"))
      (node (ref "U$2") (pin "BN1") (pinfunction "1_BN1") (pintype "bidirectional"))
      (node (ref "U$2") (pin "BN2") (pinfunction "1_BN2") (pintype "bidirectional"))
      (node (ref "U$2") (pin "BT1") (pinfunction "1_BT1") (pintype "bidirectional"))
      (node (ref "U$2") (pin "BT2") (pinfunction "1_BT2") (pintype "bidirectional"))
      (node (ref "U$2") (pin "CC1") (pinfunction "1_CC1") (pintype "bidirectional"))
      (node (ref "U$2") (pin "CC2") (pinfunction "1_CC2") (pintype "bidirectional"))
      (node (ref "U$2") (pin "CF1") (pinfunction "1_CF1") (pintype "bidirectional"))
      (node (ref "U$2") (pin "CF2") (pinfunction "1_CF2") (pintype "bidirectional"))
      (node (ref "U$2") (pin "CN1") (pinfunction "1_CN1") (pintype "bidirectional"))
      (node (ref "U$2") (pin "CN2") (pinfunction "1_CN2") (pintype "bidirectional"))
      (node (ref "U$2") (pin "CT1") (pinfunction "1_CT1") (pintype "bidirectional"))
      (node (ref "U$2") (pin "CT2") (pinfunction "1_CT2") (pintype "bidirectional"))
      (node (ref "U$2") (pin "DC1") (pinfunction "1_DC1") (pintype "bidirectional"))
      (node (ref "U$2") (pin "DC2") (pinfunction "1_DC2") (pintype "bidirectional"))
      (node (ref "U$2") (pin "DF1") (pinfunction "1_DF1") (pintype "bidirectional"))
      (node (ref "U$2") (pin "DF2") (pinfunction "1_DF2") (pintype "bidirectional"))
      (node (ref "U$2") (pin "DN1") (pinfunction "1_DN1") (pintype "bidirectional"))
      (node (ref "U$2") (pin "DN2") (pinfunction "1_DN2") (pintype "bidirectional"))
      (node (ref "U$2") (pin "DT1") (pinfunction "1_DT1") (pintype "bidirectional"))
      (node (ref "U$2") (pin "DT2") (pinfunction "1_DT2") (pintype "bidirectional"))
      (node (ref "USB_CONNECTOR") (pin "4") (pinfunction "4_4") (pintype "passive"))
      (node (ref "USB_CONNECTOR") (pin "S1") (pinfunction "S1_S1") (pintype "passive"))
      (node (ref "USB_CONNECTOR") (pin "S2") (pinfunction "S2_S2") (pintype "passive"))
    )
    (net (code "43") (name "INITIALIZE_H") (class "Default")
      (node (ref "IC8") (pin "5") (pinfunction "I_5") (pintype "input"))
      (node (ref "U$2") (pin "CR1") (pinfunction "1_CR1") (pintype "bidirectional"))
    )
    (net (code "44") (name "INITIALIZE_L") (class "Default")
      (node (ref "IC3") (pin "16") (pinfunction "IO_16") (pintype "bidirectional"))
      (node (ref "IC8") (pin "6") (pinfunction "O_6") (pintype "open_collector"))
      (node (ref "R17") (pin "2") (pinfunction "2_2") (pintype "passive"))
    )
    (net (code "45") (name "INTERNAL_IO_D") (class "Default")
      (node (ref "IC3") (pin "20") (pinfunction "IO_20") (pintype "bidirectional"))
      (node (ref "IC9") (pin "1") (pinfunction "I0_1") (pintype "input"))
      (node (ref "IC9") (pin "2") (pinfunction "I1_2") (pintype "input"))
    )
    (net (code "46") (name "INTERNAL_IO_L") (class "Default")
      (node (ref "IC9") (pin "3") (pinfunction "O_3") (pintype "open_collector"))
      (node (ref "U$2") (pin "CL1") (pinfunction "1_CL1") (pintype "bidirectional"))
    )
    (net (code "47") (name "INT_RQST_D") (class "Default")
      (node (ref "IC3") (pin "14") (pinfunction "IO_14") (pintype "bidirectional"))
      (node (ref "IC7") (pin "4") (pinfunction "I0_4") (pintype "input"))
      (node (ref "IC7") (pin "5") (pinfunction "I1_5") (pintype "input"))
    )
    (net (code "48") (name "INT_RQST_L") (class "Default")
      (node (ref "IC7") (pin "6") (pinfunction "O_6") (pintype "open_collector"))
      (node (ref "U$2") (pin "CP1") (pinfunction "1_CP1") (pintype "bidirectional"))
    )
    (net (code "49") (name "IO_PAUSE") (class "Default")
      (node (ref "IC10") (pin "6") (pinfunction "O_6") (pintype "open_collector"))
      (node (ref "IC3") (pin "28") (pinfunction "IO_28") (pintype "bidirectional"))
      (node (ref "R25") (pin "2") (pinfunction "2_2") (pintype "passive"))
    )
    (net (code "50") (name "IO_PAUSE_L") (class "Default")
      (node (ref "IC10") (pin "5") (pinfunction "I_5") (pintype "input"))
      (node (ref "U$2") (pin "CD1") (pinfunction "1_CD1") (pintype "bidirectional"))
    )
    (net (code "51") (name "K1") (class "Default")
      (node (ref "IC3") (pin "53") (pinfunction "IO_53") (pintype "bidirectional"))
      (node (ref "JP8") (pin "1") (pinfunction "1_1") (pintype "passive"))
    )
    (net (code "52") (name "K2") (class "Default")
      (node (ref "IC3") (pin "54") (pinfunction "IO_54") (pintype "bidirectional"))
      (node (ref "JP9") (pin "1") (pinfunction "1_1") (pintype "passive"))
    )
    (net (code "53") (name "K3") (class "Default")
      (node (ref "IC3") (pin "55") (pinfunction "IO_55") (pintype "bidirectional"))
      (node (ref "JP10") (pin "1") (pinfunction "1_1") (pintype "passive"))
    )
    (net (code "54") (name "K4") (class "Default")
      (node (ref "IC3") (pin "50") (pinfunction "IO_50") (pintype "bidirectional"))
      (node (ref "JP6") (pin "1") (pinfunction "1_1") (pintype "passive"))
    )
    (net (code "55") (name "K5") (class "Default")
      (node (ref "IC3") (pin "52") (pinfunction "IO_52") (pintype "bidirectional"))
      (node (ref "JP5") (pin "1") (pinfunction "1_1") (pintype "passive"))
    )
    (net (code "56") (name "K6") (class "Default")
      (node (ref "IC3") (pin "49") (pinfunction "IO_49") (pintype "bidirectional"))
      (node (ref "JP7") (pin "1") (pinfunction "1_1") (pintype "passive"))
    )
    (net (code "57") (name "LD1") (class "Default")
      (node (ref "IC3") (pin "74") (pinfunction "IO_74") (pintype "bidirectional"))
      (node (ref "R1") (pin "1") (pinfunction "1_1") (pintype "passive"))
    )
    (net (code "58") (name "LD2") (class "Default")
      (node (ref "IC3") (pin "72") (pinfunction "IO_72") (pintype "bidirectional"))
      (node (ref "R2") (pin "1") (pinfunction "1_1") (pintype "passive"))
    )
    (net (code "59") (name "LD3") (class "Default")
      (node (ref "IC3") (pin "71") (pinfunction "IO_71") (pintype "bidirectional"))
      (node (ref "R3") (pin "1") (pinfunction "1_1") (pintype "passive"))
    )
    (net (code "60") (name "MD00") (class "Default")
      (node (ref "IC14") (pin "8") (pinfunction "O_8") (pintype "open_collector"))
      (node (ref "R40") (pin "2") (pinfunction "2_2") (pintype "passive"))
    )
    (net (code "61") (name "MD00L") (class "Default")
      (node (ref "IC14") (pin "9") (pinfunction "I_9") (pintype "input"))
      (node (ref "U$2") (pin "AK1") (pinfunction "1_AK1") (pintype "bidirectional"))
    )
    (net (code "62") (name "MD01") (class "Default")
      (node (ref "IC14") (pin "10") (pinfunction "O_10") (pintype "open_collector"))
      (node (ref "R39") (pin "2") (pinfunction "2_2") (pintype "passive"))
    )
    (net (code "63") (name "MD01L") (class "Default")
      (node (ref "IC14") (pin "11") (pinfunction "I_11") (pintype "input"))
      (node (ref "U$2") (pin "AL1") (pinfunction "1_AL1") (pintype "bidirectional"))
    )
    (net (code "64") (name "MD02") (class "Default")
      (node (ref "IC14") (pin "12") (pinfunction "O_12") (pintype "open_collector"))
      (node (ref "R38") (pin "2") (pinfunction "2_2") (pintype "passive"))
    )
    (net (code "65") (name "MD02L") (class "Default")
      (node (ref "IC14") (pin "13") (pinfunction "I_13") (pintype "input"))
      (node (ref "U$2") (pin "AM1") (pinfunction "1_AM1") (pintype "bidirectional"))
    )
    (net (code "66") (name "MD03") (class "Default")
      (node (ref "IC14") (pin "6") (pinfunction "O_6") (pintype "open_collector"))
      (node (ref "IC3") (pin "42") (pinfunction "IO_42") (pintype "bidirectional"))
      (node (ref "R35") (pin "2") (pinfunction "2_2") (pintype "passive"))
    )
    (net (code "67") (name "MD03L") (class "Default")
      (node (ref "IC14") (pin "5") (pinfunction "I_5") (pintype "input"))
      (node (ref "U$2") (pin "AP1") (pinfunction "1_AP1") (pintype "bidirectional"))
    )
    (net (code "68") (name "MD04") (class "Default")
      (node (ref "IC12") (pin "8") (pinfunction "O_8") (pintype "open_collector"))
      (node (ref "IC3") (pin "41") (pinfunction "IO_41") (pintype "bidirectional"))
      (node (ref "R34") (pin "2") (pinfunction "2_2") (pintype "passive"))
    )
    (net (code "69") (name "MD04L") (class "Default")
      (node (ref "IC12") (pin "9") (pinfunction "I_9") (pintype "input"))
      (node (ref "U$2") (pin "BK1") (pinfunction "1_BK1") (pintype "bidirectional"))
    )
    (net (code "70") (name "MD05") (class "Default")
      (node (ref "IC12") (pin "6") (pinfunction "O_6") (pintype "open_collector"))
      (node (ref "IC3") (pin "37") (pinfunction "IO_37") (pintype "bidirectional"))
      (node (ref "R29") (pin "2") (pinfunction "2_2") (pintype "passive"))
    )
    (net (code "71") (name "MD05L") (class "Default")
      (node (ref "IC12") (pin "5") (pinfunction "I_5") (pintype "input"))
      (node (ref "U$2") (pin "BL1") (pinfunction "1_BL1") (pintype "bidirectional"))
    )
    (net (code "72") (name "MD06") (class "Default")
      (node (ref "IC12") (pin "4") (pinfunction "O_4") (pintype "open_collector"))
      (node (ref "IC3") (pin "39") (pinfunction "IO_39") (pintype "bidirectional"))
      (node (ref "R30") (pin "2") (pinfunction "2_2") (pintype "passive"))
    )
    (net (code "73") (name "MD06L") (class "Default")
      (node (ref "IC12") (pin "3") (pinfunction "I_3") (pintype "input"))
      (node (ref "U$2") (pin "BM1") (pinfunction "1_BM1") (pintype "bidirectional"))
    )
    (net (code "74") (name "MD07") (class "Default")
      (node (ref "IC12") (pin "2") (pinfunction "O_2") (pintype "open_collector"))
      (node (ref "IC3") (pin "40") (pinfunction "IO_40") (pintype "bidirectional"))
      (node (ref "R31") (pin "2") (pinfunction "2_2") (pintype "passive"))
    )
    (net (code "75") (name "MD07L") (class "Default")
      (node (ref "IC12") (pin "1") (pinfunction "I_1") (pintype "input"))
      (node (ref "U$2") (pin "BP1") (pinfunction "1_BP1") (pintype "bidirectional"))
    )
    (net (code "76") (name "MD08") (class "Default")
      (node (ref "IC3") (pin "13") (pinfunction "IO_13") (pintype "bidirectional"))
      (node (ref "IC6") (pin "8") (pinfunction "O_8") (pintype "open_collector"))
      (node (ref "R16") (pin "2") (pinfunction "2_2") (pintype "passive"))
    )
    (net (code "77") (name "MD08L") (class "Default")
      (node (ref "IC6") (pin "9") (pinfunction "I_9") (pintype "input"))
      (node (ref "U$2") (pin "DK1") (pinfunction "1_DK1") (pintype "bidirectional"))
    )
    (net (code "78") (name "MD09") (class "Default")
      (node (ref "IC3") (pin "10") (pinfunction "IO_10") (pintype "bidirectional"))
      (node (ref "IC6") (pin "6") (pinfunction "O_6") (pintype "open_collector"))
      (node (ref "R11") (pin "2") (pinfunction "2_2") (pintype "passive"))
    )
    (net (code "79") (name "MD09L") (class "Default")
      (node (ref "IC6") (pin "5") (pinfunction "I_5") (pintype "input"))
      (node (ref "U$2") (pin "DL1") (pinfunction "1_DL1") (pintype "bidirectional"))
    )
    (net (code "80") (name "MD10") (class "Default")
      (node (ref "IC3") (pin "11") (pinfunction "IO_11") (pintype "bidirectional"))
      (node (ref "IC6") (pin "4") (pinfunction "O_4") (pintype "open_collector"))
      (node (ref "R12") (pin "2") (pinfunction "2_2") (pintype "passive"))
    )
    (net (code "81") (name "MD10L") (class "Default")
      (node (ref "IC6") (pin "3") (pinfunction "I_3") (pintype "input"))
      (node (ref "U$2") (pin "DM1") (pinfunction "1_DM1") (pintype "bidirectional"))
    )
    (net (code "82") (name "MD11") (class "Default")
      (node (ref "IC3") (pin "12") (pinfunction "IO_12") (pintype "bidirectional"))
      (node (ref "IC6") (pin "2") (pinfunction "O_2") (pintype "open_collector"))
      (node (ref "R13") (pin "2") (pinfunction "2_2") (pintype "passive"))
    )
    (net (code "83") (name "MD11L") (class "Default")
      (node (ref "IC6") (pin "1") (pinfunction "I_1") (pintype "input"))
      (node (ref "U$2") (pin "DP1") (pinfunction "1_DP1") (pintype "bidirectional"))
    )
    (net (code "84") (name "Net-(C119-Pad1)") (class "Default")
      (node (ref "C119") (pin "1") (pinfunction "1_1") (pintype "passive"))
      (node (ref "L100") (pin "2") (pinfunction "2_2") (pintype "passive"))
      (node (ref "USB_CONNECTOR") (pin "1") (pinfunction "1_1") (pintype "passive"))
    )
    (net (code "85") (name "Net-(D1-PadA)") (class "Default")
      (node (ref "D1") (pin "A") (pinfunction "A_A") (pintype "passive"))
      (node (ref "JP2") (pin "1") (pinfunction "1_1") (pintype "passive"))
      (node (ref "L100") (pin "1") (pinfunction "1_1") (pintype "passive"))
    )
    (net (code "86") (name "Net-(IC1A-D0)") (class "Default")
      (node (ref "IC1") (pin "24") (pinfunction "D0_24") (pintype "bidirectional"))
      (node (ref "IC3") (pin "90") (pinfunction "IO_90") (pintype "bidirectional"))
    )
    (net (code "87") (name "Net-(IC1A-D1)") (class "Default")
      (node (ref "IC1") (pin "4") (pinfunction "D1_4") (pintype "bidirectional"))
      (node (ref "IC3") (pin "86") (pinfunction "IO_86") (pintype "bidirectional"))
    )
    (net (code "88") (name "Net-(IC1A-D2)") (class "Default")
      (node (ref "IC1") (pin "2") (pinfunction "D2_2") (pintype "bidirectional"))
      (node (ref "IC3") (pin "87") (pinfunction "IO_87") (pintype "bidirectional"))
    )
    (net (code "89") (name "Net-(IC1A-D3)") (class "Default")
      (node (ref "IC1") (pin "9") (pinfunction "D3_9") (pintype "bidirectional"))
      (node (ref "IC3") (pin "79") (pinfunction "IO_79") (pintype "bidirectional"))
    )
    (net (code "90") (name "Net-(IC1A-D4)") (class "Default")
      (node (ref "IC1") (pin "1") (pinfunction "D4_1") (pintype "bidirectional"))
      (node (ref "IC3") (pin "89") (pinfunction "IO_89") (pintype "bidirectional"))
    )
    (net (code "91") (name "Net-(IC1A-D5)") (class "Default")
      (node (ref "IC1") (pin "7") (pinfunction "D5_7") (pintype "bidirectional"))
      (node (ref "IC3") (pin "82") (pinfunction "IO_82") (pintype "bidirectional"))
    )
    (net (code "92") (name "Net-(IC1A-D6)") (class "Default")
      (node (ref "IC1") (pin "8") (pinfunction "D6_8") (pintype "bidirectional"))
      (node (ref "IC3") (pin "81") (pinfunction "IO_81") (pintype "bidirectional"))
    )
    (net (code "93") (name "Net-(IC1A-D7)") (class "Default")
      (node (ref "IC1") (pin "5") (pinfunction "D7_5") (pintype "bidirectional"))
      (node (ref "IC3") (pin "85") (pinfunction "IO_85") (pintype "bidirectional"))
    )
    (net (code "94") (name "Net-(IC1A-WR)") (class "Default")
      (node (ref "IC1") (pin "12") (pinfunction "WR_12") (pintype "bidirectional"))
      (node (ref "IC3") (pin "76") (pinfunction "IO_76") (pintype "bidirectional"))
    )
    (net (code "95") (name "Net-(IC1A-{slash}RD)") (class "Default")
      (node (ref "IC1") (pin "11") (pinfunction "/RD_11") (pintype "bidirectional"))
      (node (ref "IC3") (pin "77") (pinfunction "IO_77") (pintype "bidirectional"))
    )
    (net (code "96") (name "Net-(IC1A-{slash}RXF)") (class "Default")
      (node (ref "IC1") (pin "21") (pinfunction "/RXF_21") (pintype "bidirectional"))
      (node (ref "IC3") (pin "93") (pinfunction "IO_93") (pintype "bidirectional"))
    )
    (net (code "97") (name "Net-(IC1A-{slash}TXE)") (class "Default")
      (node (ref "IC1") (pin "20") (pinfunction "/TXE_20") (pintype "bidirectional"))
      (node (ref "IC3") (pin "94") (pinfunction "IO_94") (pintype "bidirectional"))
    )
    (net (code "98") (name "Net-(IC1B-CBUS5)") (class "Default")
      (node (ref "IC1") (pin "23") (pinfunction "CBUS5_23") (pintype "bidirectional"))
      (node (ref "IC3") (pin "91") (pinfunction "IO_91") (pintype "bidirectional"))
    )
    (net (code "99") (name "Net-(IC1B-CBUS6)") (class "Default")
      (node (ref "IC1") (pin "22") (pinfunction "CBUS6_22") (pintype "bidirectional"))
      (node (ref "IC3") (pin "92") (pinfunction "IO_92") (pintype "bidirectional"))
    )
    (net (code "100") (name "Net-(IC1B-{slash}RESET)") (class "Default")
      (node (ref "IC1") (pin "16") (pinfunction "/RESET_16") (pintype "bidirectional"))
      (node (ref "IC3") (pin "95") (pinfunction "IO_95") (pintype "bidirectional"))
    )
    (net (code "101") (name "Net-(IC1B-{slash}SIWU)") (class "Default")
      (node (ref "IC1") (pin "10") (pinfunction "/SIWU_10") (pintype "bidirectional"))
      (node (ref "IC3") (pin "78") (pinfunction "IO_78") (pintype "bidirectional"))
    )
    (net (code "102") (name "Net-(IC1D-USBDM)") (class "Default")
      (node (ref "C120") (pin "1") (pinfunction "1_1") (pintype "passive"))
      (node (ref "IC1") (pin "14") (pinfunction "USBDM_14") (pintype "bidirectional"))
      (node (ref "R100") (pin "2") (pinfunction "2_2") (pintype "passive"))
    )
    (net (code "103") (name "Net-(IC1D-USBDP)") (class "Default")
      (node (ref "C121") (pin "1") (pinfunction "1_1") (pintype "passive"))
      (node (ref "IC1") (pin "13") (pinfunction "USBDP_13") (pintype "bidirectional"))
      (node (ref "R101") (pin "2") (pinfunction "2_2") (pintype "passive"))
    )
    (net (code "104") (name "Net-(IC4F-I)") (class "Default")
      (node (ref "IC4") (pin "13") (pinfunction "I_13") (pintype "input"))
      (node (ref "JP12") (pin "1") (pinfunction "1_1") (pintype "passive"))
    )
    (net (code "105") (name "Net-(IC6E-I)") (class "Default")
      (node (ref "IC6") (pin "11") (pinfunction "I_11") (pintype "input"))
      (node (ref "JP17") (pin "1") (pinfunction "1_1") (pintype "passive"))
    )
    (net (code "106") (name "Net-(IC6F-I)") (class "Default")
      (node (ref "IC6") (pin "13") (pinfunction "I_13") (pintype "input"))
      (node (ref "JP13") (pin "1") (pinfunction "1_1") (pintype "passive"))
    )
    (net (code "107") (name "Net-(IC7C-O)") (class "Default")
      (node (ref "IC7") (pin "8") (pinfunction "O_8") (pintype "open_collector"))
      (node (ref "JP20") (pin "1") (pinfunction "1_1") (pintype "passive"))
    )
    (net (code "108") (name "Net-(IC7D-O)") (class "Default")
      (node (ref "IC7") (pin "11") (pinfunction "O_11") (pintype "open_collector"))
      (node (ref "JP18") (pin "1") (pinfunction "1_1") (pintype "passive"))
    )
    (net (code "109") (name "Net-(IC8A-I)") (class "Default")
      (node (ref "IC8") (pin "1") (pinfunction "I_1") (pintype "input"))
      (node (ref "JP11") (pin "1") (pinfunction "1_1") (pintype "passive"))
    )
    (net (code "110") (name "Net-(IC8B-I)") (class "Default")
      (node (ref "IC8") (pin "3") (pinfunction "I_3") (pintype "input"))
      (node (ref "JP15") (pin "1") (pinfunction "1_1") (pintype "passive"))
    )
    (net (code "111") (name "Net-(IC8E-I)") (class "Default")
      (node (ref "IC8") (pin "11") (pinfunction "I_11") (pintype "input"))
      (node (ref "JP19") (pin "1") (pinfunction "1_1") (pintype "passive"))
    )
    (net (code "112") (name "Net-(IC8F-I)") (class "Default")
      (node (ref "IC8") (pin "13") (pinfunction "I_13") (pintype "input"))
      (node (ref "JP14") (pin "1") (pinfunction "1_1") (pintype "passive"))
    )
    (net (code "113") (name "Net-(IC11A-O)") (class "Default")
      (node (ref "IC11") (pin "3") (pinfunction "O_3") (pintype "open_collector"))
      (node (ref "JP16") (pin "1") (pinfunction "1_1") (pintype "passive"))
    )
    (net (code "114") (name "Net-(LED1-PadA)") (class "Default")
      (node (ref "LED1") (pin "A") (pinfunction "A_A") (pintype "passive"))
      (node (ref "R1") (pin "2") (pinfunction "2_2") (pintype "passive"))
    )
    (net (code "115") (name "Net-(LED2-PadA)") (class "Default")
      (node (ref "LED2") (pin "A") (pinfunction "A_A") (pintype "passive"))
      (node (ref "R2") (pin "2") (pinfunction "2_2") (pintype "passive"))
    )
    (net (code "116") (name "Net-(LED3-PadA)") (class "Default")
      (node (ref "LED3") (pin "A") (pinfunction "A_A") (pintype "passive"))
      (node (ref "R3") (pin "2") (pinfunction "2_2") (pintype "passive"))
    )
    (net (code "117") (name "Net-(LED4-PadA)") (class "Default")
      (node (ref "LED4") (pin "A") (pinfunction "A_A") (pintype "passive"))
      (node (ref "R4") (pin "2") (pinfunction "2_2") (pintype "passive"))
    )
    (net (code "118") (name "Net-(R100-Pad1)") (class "Default")
      (node (ref "R100") (pin "1") (pinfunction "1_1") (pintype "passive"))
      (node (ref "USB_CONNECTOR") (pin "2") (pinfunction "2_2") (pintype "passive"))
    )
    (net (code "119") (name "Net-(R101-Pad1)") (class "Default")
      (node (ref "R101") (pin "1") (pinfunction "1_1") (pintype "passive"))
      (node (ref "USB_CONNECTOR") (pin "3") (pinfunction "3_3") (pintype "passive"))
    )
    (net (code "120") (name "RX_ADDR_0") (class "Default")
      (node (ref "IC3") (pin "64") (pinfunction "IO_64") (pintype "bidirectional"))
      (node (ref "R41") (pin "1") (pinfunction "1_1") (pintype "passive"))
      (node (ref "S1") (pin "6") (pinfunction "6_6") (pintype "passive"))
    )
    (net (code "121") (name "RX_ADDR_1") (class "Default")
      (node (ref "IC3") (pin "65") (pinfunction "IO_65") (pintype "bidirectional"))
      (node (ref "R42") (pin "1") (pinfunction "1_1") (pintype "passive"))
      (node (ref "S1") (pin "5") (pinfunction "5_5") (pintype "passive"))
    )
    (net (code "122") (name "RX_ADDR_2") (class "Default")
      (node (ref "IC3") (pin "66") (pinfunction "IO_66") (pintype "bidirectional"))
      (node (ref "R43") (pin "1") (pinfunction "1_1") (pintype "passive"))
      (node (ref "S1") (pin "4") (pinfunction "4_4") (pintype "passive"))
    )
    (net (code "123") (name "RX_ADDR_3") (class "Default")
      (node (ref "IC3") (pin "67") (pinfunction "IO_67") (pintype "bidirectional"))
      (node (ref "R44") (pin "1") (pinfunction "1_1") (pintype "passive"))
      (node (ref "S1") (pin "3") (pinfunction "3_3") (pintype "passive"))
    )
    (net (code "124") (name "RX_ADDR_4") (class "Default")
      (node (ref "IC3") (pin "68") (pinfunction "IO_68") (pintype "bidirectional"))
      (node (ref "R45") (pin "1") (pinfunction "1_1") (pintype "passive"))
      (node (ref "S1") (pin "2") (pinfunction "2_2") (pintype "passive"))
    )
    (net (code "125") (name "RX_ADDR_5") (class "Default")
      (node (ref "IC3") (pin "70") (pinfunction "IO_70") (pintype "bidirectional"))
      (node (ref "R46") (pin "1") (pinfunction "1_1") (pintype "passive"))
      (node (ref "S1") (pin "1") (pinfunction "1_1") (pintype "passive"))
    )
    (net (code "126") (name "SKIP_D") (class "Default")
      (node (ref "IC3") (pin "15") (pinfunction "IO_15") (pintype "bidirectional"))
      (node (ref "IC7") (pin "1") (pinfunction "I0_1") (pintype "input"))
      (node (ref "IC7") (pin "2") (pinfunction "I1_2") (pintype "input"))
    )
    (net (code "127") (name "SKIP_L") (class "Default")
      (node (ref "IC7") (pin "3") (pinfunction "O_3") (pintype "open_collector"))
      (node (ref "U$2") (pin "CS1") (pinfunction "1_CS1") (pintype "bidirectional"))
    )
    (net (code "128") (name "SPARE0_D") (class "Default")
      (node (ref "IC7") (pin "10") (pinfunction "I1_10") (pintype "input"))
      (node (ref "IC7") (pin "9") (pinfunction "I0_9") (pintype "input"))
    )
    (net (code "129") (name "SPARE1_D") (class "Default")
      (node (ref "IC7") (pin "12") (pinfunction "I0_12") (pintype "input"))
      (node (ref "IC7") (pin "13") (pinfunction "I1_13") (pintype "input"))
    )
    (net (code "130") (name "SPARE2_D") (class "Default")
      (node (ref "IC11") (pin "1") (pinfunction "I0_1") (pintype "input"))
      (node (ref "IC11") (pin "2") (pinfunction "I1_2") (pintype "input"))
    )
    (net (code "131") (name "SPARE3_R") (class "Default")
      (node (ref "IC4") (pin "12") (pinfunction "O_12") (pintype "open_collector"))
      (node (ref "R8") (pin "2") (pinfunction "2_2") (pintype "passive"))
    )
    (net (code "132") (name "SPARE4_R") (class "Default")
      (node (ref "IC6") (pin "10") (pinfunction "O_10") (pintype "open_collector"))
      (node (ref "R15") (pin "2") (pinfunction "2_2") (pintype "passive"))
    )
    (net (code "133") (name "SPARE5_R") (class "Default")
      (node (ref "IC6") (pin "12") (pinfunction "O_12") (pintype "open_collector"))
      (node (ref "R14") (pin "2") (pinfunction "2_2") (pintype "passive"))
    )
    (net (code "134") (name "SPARE6_R") (class "Default")
      (node (ref "IC8") (pin "2") (pinfunction "O_2") (pintype "open_collector"))
      (node (ref "R19") (pin "2") (pinfunction "2_2") (pintype "passive"))
    )
    (net (code "135") (name "SPARE7_R") (class "Default")
      (node (ref "IC8") (pin "4") (pinfunction "O_4") (pintype "open_collector"))
      (node (ref "R18") (pin "2") (pinfunction "2_2") (pintype "passive"))
    )
    (net (code "136") (name "SPARE8_R") (class "Default")
      (node (ref "IC8") (pin "10") (pinfunction "O_10") (pintype "open_collector"))
      (node (ref "R21") (pin "2") (pinfunction "2_2") (pintype "passive"))
    )
    (net (code "137") (name "SPARE9_R") (class "Default")
      (node (ref "IC8") (pin "12") (pinfunction "O_12") (pintype "open_collector"))
      (node (ref "R20") (pin "2") (pinfunction "2_2") (pintype "passive"))
    )
    (net (code "138") (name "SW") (class "Default")
      (node (ref "IC4") (pin "3") (pinfunction "I_3") (pintype "input"))
      (node (ref "U$2") (pin "DV2") (pinfunction "1_DV2") (pintype "bidirectional"))
    )
    (net (code "139") (name "SWL") (class "Default")
      (node (ref "IC3") (pin "97") (pinfunction "IO_97") (pintype "bidirectional"))
      (node (ref "IC4") (pin "4") (pinfunction "O_4") (pintype "open_collector"))
      (node (ref "R6") (pin "2") (pinfunction "2_2") (pintype "passive"))
    )
    (net (code "140") (name "TCK") (class "Default")
      (node (ref "IC3") (pin "48") (pinfunction "TCK_48") (pintype "bidirectional"))
      (node (ref "JP1") (pin "4") (pinfunction "4_4") (pintype "passive"))
    )
    (net (code "141") (name "TDI") (class "Default")
      (node (ref "IC3") (pin "45") (pinfunction "TDI_45") (pintype "bidirectional"))
      (node (ref "JP1") (pin "2") (pinfunction "2_2") (pintype "passive"))
    )
    (net (code "142") (name "TDO") (class "Default")
      (node (ref "IC3") (pin "83") (pinfunction "TDO_83") (pintype "bidirectional"))
      (node (ref "JP1") (pin "3") (pinfunction "3_3") (pintype "passive"))
    )
    (net (code "143") (name "TMS") (class "Default")
      (node (ref "IC3") (pin "47") (pinfunction "TMS_47") (pintype "bidirectional"))
      (node (ref "JP1") (pin "1") (pinfunction "1_1") (pintype "passive"))
    )
    (net (code "144") (name "TP3H") (class "Default")
      (node (ref "IC10") (pin "3") (pinfunction "I_3") (pintype "input"))
      (node (ref "U$2") (pin "CH2") (pinfunction "1_CH2") (pintype "bidirectional"))
    )
    (net (code "145") (name "TP3_L") (class "Default")
      (node (ref "IC10") (pin "4") (pinfunction "O_4") (pintype "open_collector"))
      (node (ref "IC3") (pin "25") (pinfunction "IO_25") (pintype "bidirectional"))
      (node (ref "R23") (pin "2") (pinfunction "2_2") (pintype "passive"))
    )
    (net (code "146") (name "TS3") (class "Default")
      (node (ref "IC3") (pin "17") (pinfunction "IO_17") (pintype "bidirectional"))
      (node (ref "IC8") (pin "8") (pinfunction "O_8") (pintype "open_collector"))
      (node (ref "R22") (pin "2") (pinfunction "2_2") (pintype "passive"))
    )
    (net (code "147") (name "TS3L") (class "Default")
      (node (ref "IC8") (pin "9") (pinfunction "I_9") (pintype "input"))
      (node (ref "U$2") (pin "CM2") (pinfunction "1_CM2") (pintype "bidirectional"))
    )
    (net (code "148") (name "TX_ADDR_0") (class "Default")
      (node (ref "IC3") (pin "56") (pinfunction "IO_56") (pintype "bidirectional"))
      (node (ref "R47") (pin "1") (pinfunction "1_1") (pintype "passive"))
      (node (ref "S2") (pin "6") (pinfunction "6_6") (pintype "passive"))
    )
    (net (code "149") (name "TX_ADDR_1") (class "Default")
      (node (ref "IC3") (pin "58") (pinfunction "IO_58") (pintype "bidirectional"))
      (node (ref "R48") (pin "1") (pinfunction "1_1") (pintype "passive"))
      (node (ref "S2") (pin "5") (pinfunction "5_5") (pintype "passive"))
    )
    (net (code "150") (name "TX_ADDR_2") (class "Default")
      (node (ref "IC3") (pin "59") (pinfunction "IO_59") (pintype "bidirectional"))
      (node (ref "R49") (pin "1") (pinfunction "1_1") (pintype "passive"))
      (node (ref "S2") (pin "4") (pinfunction "4_4") (pintype "passive"))
    )
    (net (code "151") (name "TX_ADDR_3") (class "Default")
      (node (ref "IC3") (pin "60") (pinfunction "IO_60") (pintype "bidirectional"))
      (node (ref "R50") (pin "1") (pinfunction "1_1") (pintype "passive"))
      (node (ref "S2") (pin "3") (pinfunction "3_3") (pintype "passive"))
    )
    (net (code "152") (name "TX_ADDR_4") (class "Default")
      (node (ref "IC3") (pin "61") (pinfunction "IO_61") (pintype "bidirectional"))
      (node (ref "R51") (pin "1") (pinfunction "1_1") (pintype "passive"))
      (node (ref "S2") (pin "2") (pinfunction "2_2") (pintype "passive"))
    )
    (net (code "153") (name "TX_ADDR_5") (class "Default")
      (node (ref "IC3") (pin "63") (pinfunction "IO_63") (pintype "bidirectional"))
      (node (ref "R52") (pin "1") (pinfunction "1_1") (pintype "passive"))
      (node (ref "S2") (pin "1") (pinfunction "1_1") (pintype "passive"))
    )
    (net (code "154") (name "VCC") (class "Default")
      (node (ref "C100") (pin "1") (pinfunction "1_1") (pintype "passive"))
      (node (ref "C101") (pin "1") (pinfunction "1_1") (pintype "passive"))
      (node (ref "C102") (pin "1") (pinfunction "1_1") (pintype "passive"))
      (node (ref "C103") (pin "1") (pinfunction "1_1") (pintype "passive"))
      (node (ref "C104") (pin "1") (pinfunction "1_1") (pintype "passive"))
      (node (ref "C105") (pin "1") (pinfunction "1_1") (pintype "passive"))
      (node (ref "C106") (pin "1") (pinfunction "1_1") (pintype "passive"))
      (node (ref "C107") (pin "1") (pinfunction "1_1") (pintype "passive"))
      (node (ref "C108") (pin "1") (pinfunction "1_1") (pintype "passive"))
      (node (ref "C109") (pin "1") (pinfunction "1_1") (pintype "passive"))
      (node (ref "C110") (pin "1") (pinfunction "1_1") (pintype "passive"))
      (node (ref "D2") (pin "A") (pinfunction "A_A") (pintype "passive"))
      (node (ref "JP4") (pin "1") (pinfunction "1_1") (pintype "passive"))
      (node (ref "U$2") (pin "AA2") (pinfunction "1_AA2") (pintype "bidirectional"))
      (node (ref "U$2") (pin "BA2") (pinfunction "1_BA2") (pintype "bidirectional"))
      (node (ref "U$2") (pin "CA2") (pinfunction "1_CA2") (pintype "bidirectional"))
    )
    (net (code "155") (name "V_UNREG") (class "Default")
      (node (ref "D1") (pin "C") (pinfunction "C_C") (pintype "passive"))
      (node (ref "D2") (pin "C") (pinfunction "C_C") (pintype "passive"))
      (node (ref "IC2") (pin "3") (pinfunction "IN_3") (pintype "input"))
      (node (ref "JP3") (pin "1") (pinfunction "1_1") (pintype "passive"))
    )
    (net (code "156") (name "unconnected-(IC1C-VCORE-Pad17)") (class "Default")
      (node (ref "IC1") (pin "17") (pinfunction "VCORE_17") (pintype "passive"))
    )
  )
)
